# SparkFun_RTK_Facet_L-Band_-_Main.net
KiCad netlist of a schematic drawn in EAGLE
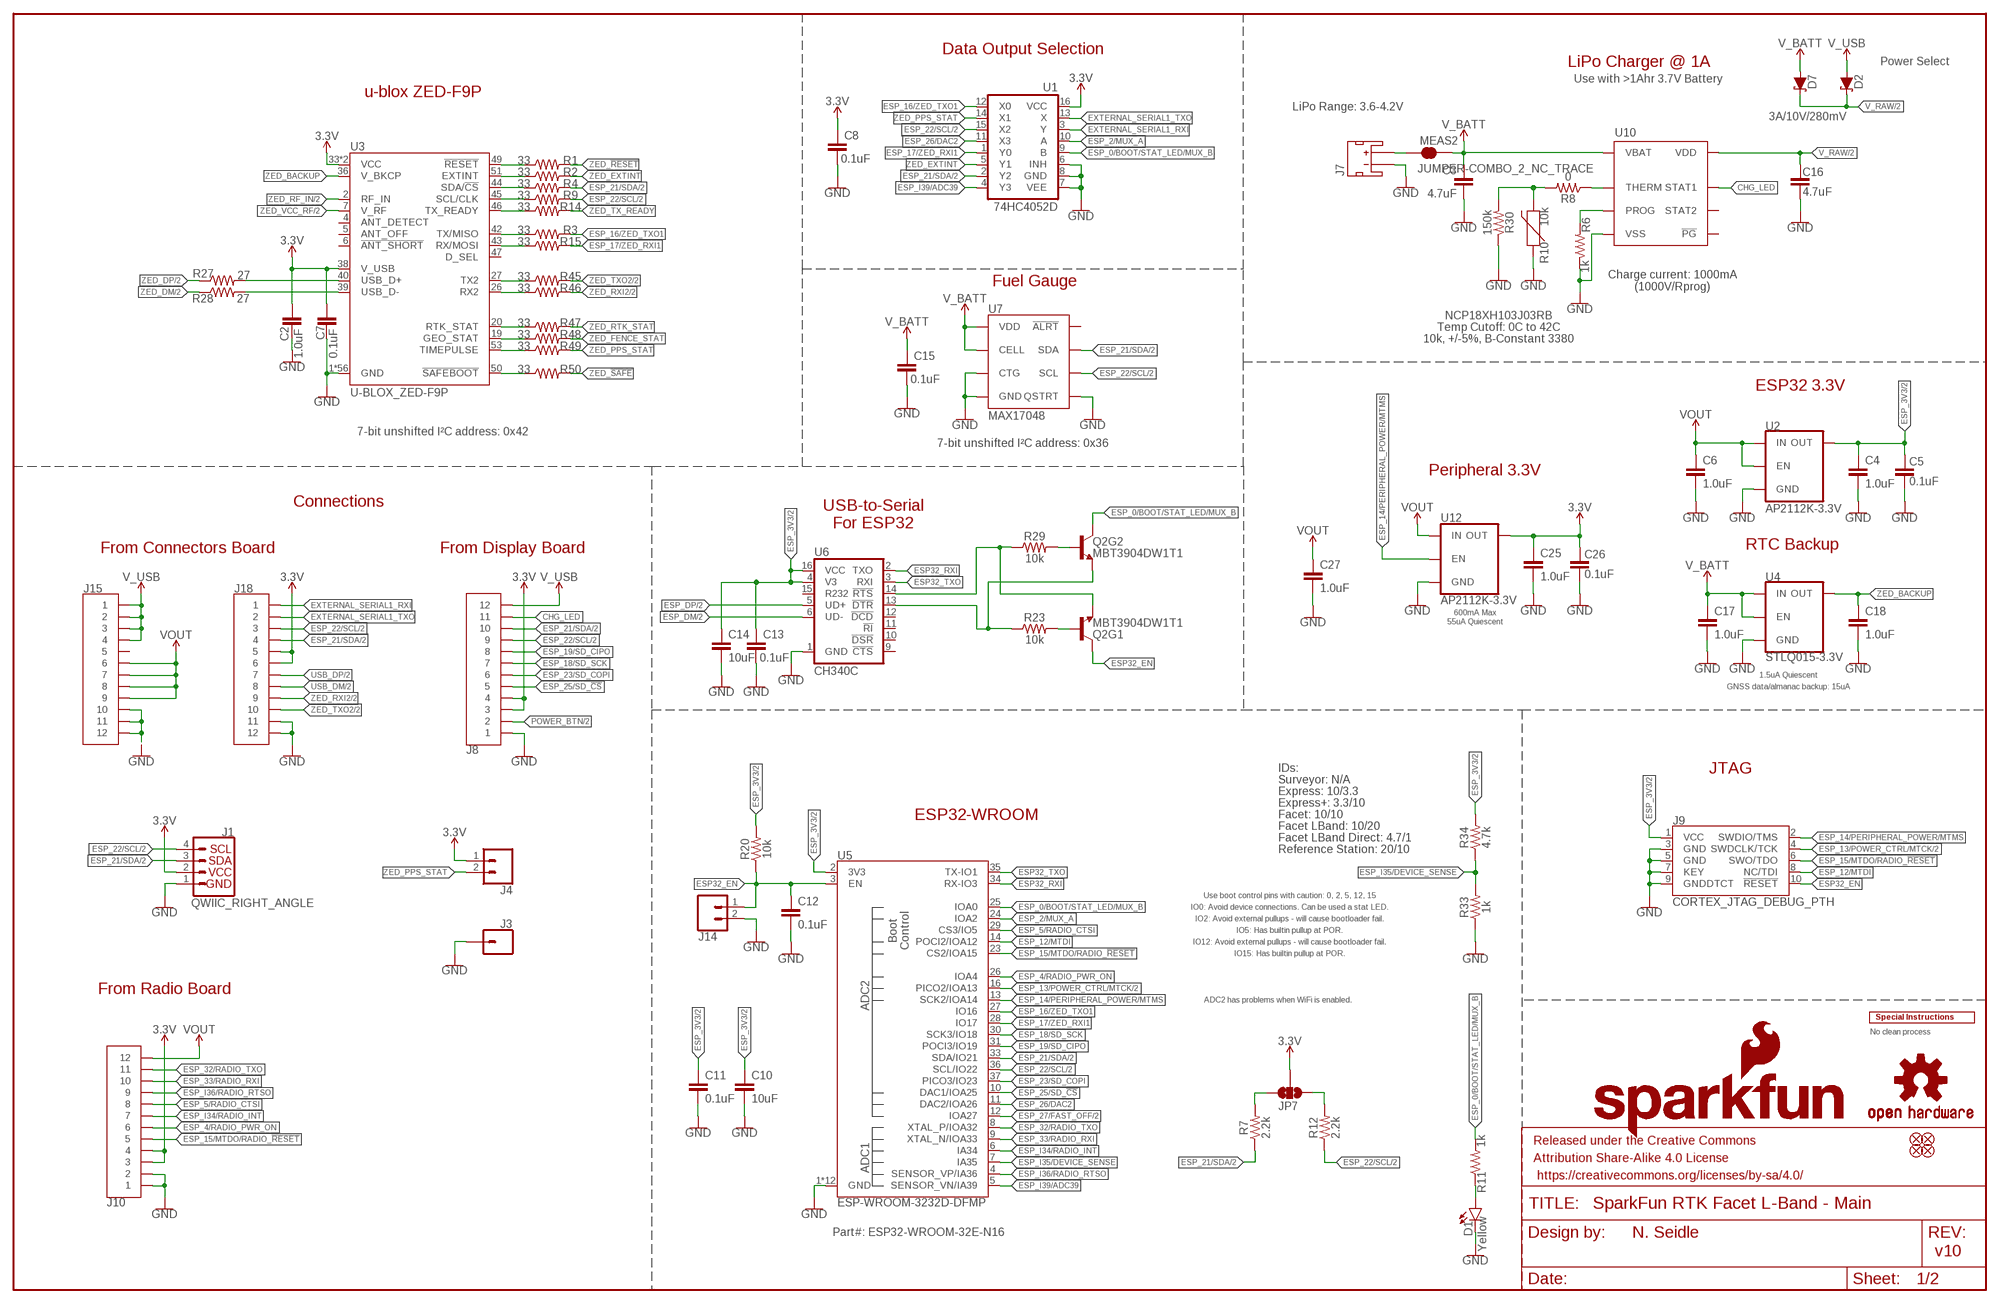
[diagram p0: schematic, sheet 1]
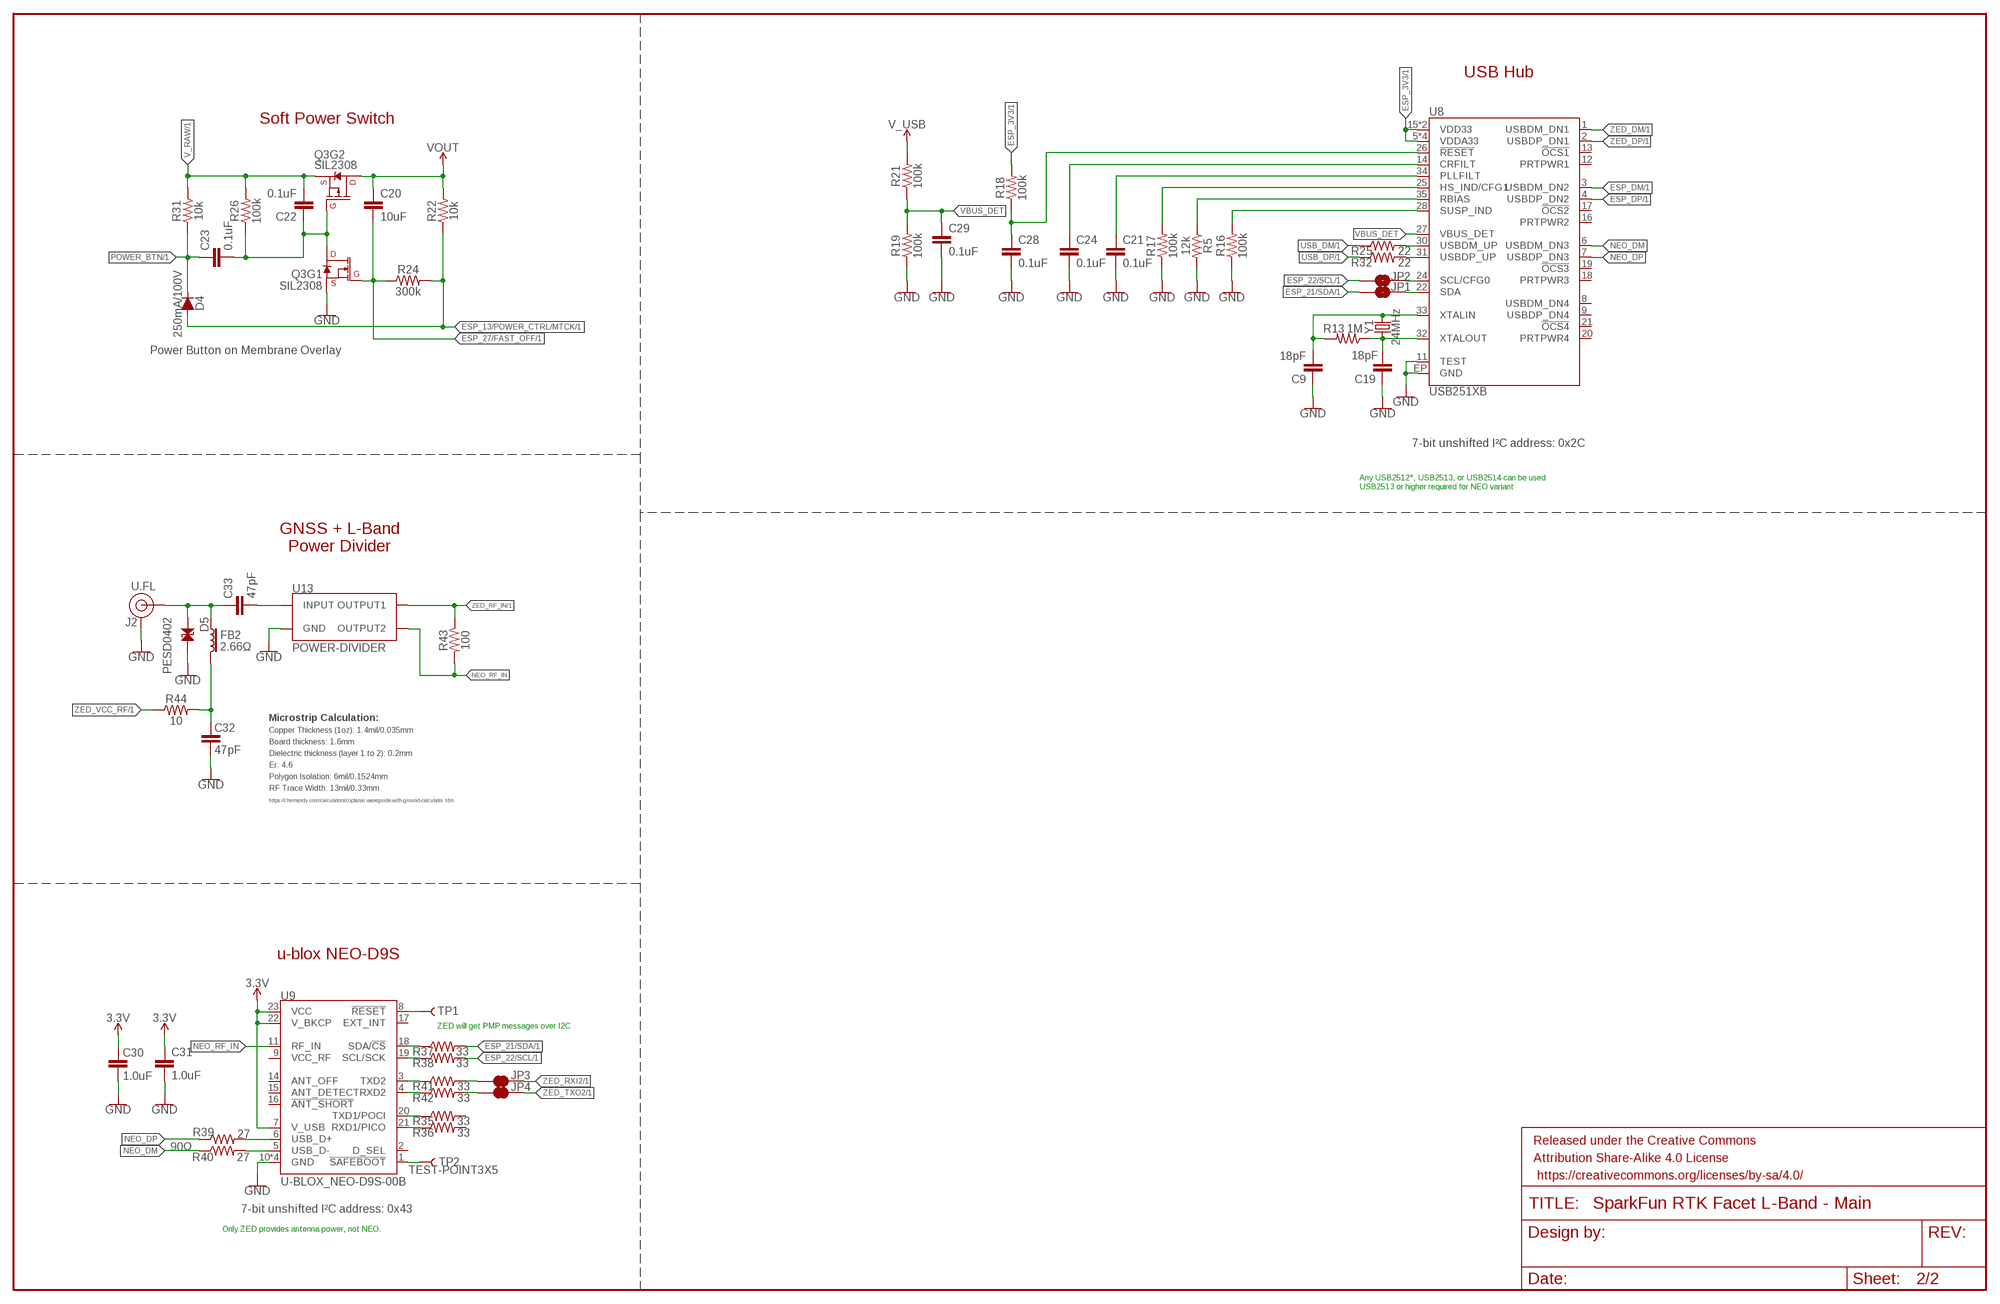
[diagram p1: schematic, sheet 2]

(export (version "E")
  (design (tool "Eeschema 10.0.6"))
  (components
    (comp (ref "C2")
      (value "1.0uF")
      (footprint "eagle-import:0603")
      (libsource (lib "eagle-import") (part "1.0UF-0603-16V-10%-X7R"))
    )
    (comp (ref "C3")
      (value "4.7uF")
      (footprint "eagle-import:0603")
      (libsource (lib "eagle-import") (part "4.7UF-0603-35V-(20%)"))
    )
    (comp (ref "C4")
      (value "1.0uF")
      (footprint "eagle-import:0603")
      (libsource (lib "eagle-import") (part "1.0UF-0603-16V-10%-X7R"))
    )
    (comp (ref "C5")
      (value "0.1uF")
      (footprint "eagle-import:0603")
      (libsource (lib "eagle-import") (part "0.1UF-0603-25V-5%"))
    )
    (comp (ref "C6")
      (value "1.0uF")
      (footprint "eagle-import:0603")
      (libsource (lib "eagle-import") (part "1.0UF-0603-16V-10%-X7R"))
    )
    (comp (ref "C7")
      (value "0.1uF")
      (footprint "eagle-import:0603")
      (libsource (lib "eagle-import") (part "0.1UF-0603-25V-5%"))
    )
    (comp (ref "C8")
      (value "0.1uF")
      (footprint "eagle-import:0603")
      (libsource (lib "eagle-import") (part "0.1UF-0603-25V-(+80/-20%)"))
    )
    (comp (ref "C10")
      (value "10uF")
      (footprint "eagle-import:0603")
      (libsource (lib "eagle-import") (part "10UF-0603-6.3V-20%"))
    )
    (comp (ref "C11")
      (value "0.1uF")
      (footprint "eagle-import:0603")
      (libsource (lib "eagle-import") (part "0.1UF-0603-25V-(+80/-20%)"))
    )
    (comp (ref "C12")
      (value "0.1uF")
      (footprint "eagle-import:0603")
      (libsource (lib "eagle-import") (part "0.1UF-0603-25V-(+80/-20%)"))
    )
    (comp (ref "C13")
      (value "0.1uF")
      (footprint "eagle-import:0603")
      (libsource (lib "eagle-import") (part "0.1UF-0603-25V-(+80/-20%)"))
    )
    (comp (ref "C14")
      (value "10uF")
      (footprint "eagle-import:0603")
      (libsource (lib "eagle-import") (part "10UF-0603-6.3V-20%"))
    )
    (comp (ref "C15")
      (value "0.1uF")
      (footprint "eagle-import:0603")
      (libsource (lib "eagle-import") (part "0.1UF-0603-25V-(+80/-20%)"))
    )
    (comp (ref "C16")
      (value "4.7uF")
      (footprint "eagle-import:0603")
      (libsource (lib "eagle-import") (part "4.7UF-0603-35V-(20%)"))
    )
    (comp (ref "C17")
      (value "1.0uF")
      (footprint "eagle-import:0603")
      (libsource (lib "eagle-import") (part "1.0UF-0603-16V-10%-X7R"))
    )
    (comp (ref "C18")
      (value "1.0uF")
      (footprint "eagle-import:0603")
      (libsource (lib "eagle-import") (part "1.0UF-0603-16V-10%-X7R"))
    )
    (comp (ref "C25")
      (value "1.0uF")
      (footprint "eagle-import:0603")
      (libsource (lib "eagle-import") (part "1.0UF-0603-16V-10%-X7R"))
    )
    (comp (ref "C26")
      (value "0.1uF")
      (footprint "eagle-import:0603")
      (libsource (lib "eagle-import") (part "0.1UF-0603-25V-5%"))
    )
    (comp (ref "C27")
      (value "1.0uF")
      (footprint "eagle-import:0603")
      (libsource (lib "eagle-import") (part "1.0UF-0603-16V-10%-X7R"))
    )
    (comp (ref "D1")
      (value "Yellow")
      (footprint "eagle-import:LED-0603")
      (libsource (lib "eagle-import") (part "LED-YELLOW0603"))
    )
    (comp (ref "D2")
      (value "3A/10V/280mV")
      (footprint "eagle-import:SOD-323")
      (libsource (lib "eagle-import") (part "DIODE-SCHOTTKY-BAT60A"))
    )
    (comp (ref "D7")
      (value "3A/10V/280mV")
      (footprint "eagle-import:SOD-323")
      (libsource (lib "eagle-import") (part "DIODE-SCHOTTKY-BAT60A"))
    )
    (comp (ref "FRAME2")
      (value "FRAME-LEDGER")
      (footprint "eagle-import:CREATIVE_COMMONS")
      (libsource (lib "eagle-import") (part "FRAME-LEDGER"))
    )
    (comp (ref "J1")
      (value "QWIIC_RIGHT_ANGLE")
      (footprint "eagle-import:JST04_1MM_RA")
      (libsource (lib "eagle-import") (part "QWIIC_CONNECTORJS-1MM"))
    )
    (comp (ref "J3")
      (value "CONN_01PTH_NO_SILK_YES_STOP")
      (footprint "eagle-import:1X01_NO_SILK")
      (libsource (lib "eagle-import") (part "CONN_01PTH_NO_SILK_YES_STOP"))
    )
    (comp (ref "J4")
      (value "CONN_021X02_NO_SILK")
      (footprint "eagle-import:1X02_NO_SILK")
      (libsource (lib "eagle-import") (part "CONN_021X02_NO_SILK"))
    )
    (comp (ref "J7")
      (value "JST_2MM_MALE")
      (footprint "eagle-import:JST-2-SMD")
      (libsource (lib "eagle-import") (part "JST_2MM_MALE"))
    )
    (comp (ref "J8")
      (value "FPC_12_0.5MM_BACKFLIP")
      (footprint "eagle-import:FPC_12_DOUBLESIDED_BACKFLIP")
      (libsource (lib "eagle-import") (part "FPC_12_0.5MM_BACKFLIP"))
    )
    (comp (ref "J9")
      (value "CORTEX_JTAG_DEBUG_PTH")
      (footprint "eagle-import:2X5-PTH-1.27MM")
      (libsource (lib "eagle-import") (part "CORTEX_JTAG_DEBUG_PTH"))
    )
    (comp (ref "J10")
      (value "FPC_12_0.5MM_BACKFLIP")
      (footprint "eagle-import:FPC_12_DOUBLESIDED_BACKFLIP")
      (libsource (lib "eagle-import") (part "FPC_12_0.5MM_BACKFLIP"))
    )
    (comp (ref "J14")
      (value "CONN_021X02_NO_SILK")
      (footprint "eagle-import:1X02_NO_SILK")
      (libsource (lib "eagle-import") (part "CONN_021X02_NO_SILK"))
    )
    (comp (ref "J15")
      (value "FPC_12_0.5MM_BACKFLIP")
      (footprint "eagle-import:FPC_12_DOUBLESIDED_BACKFLIP")
      (libsource (lib "eagle-import") (part "FPC_12_0.5MM_BACKFLIP"))
    )
    (comp (ref "J18")
      (value "FPC_12_0.5MM_BACKFLIP")
      (footprint "eagle-import:FPC_12_DOUBLESIDED_BACKFLIP")
      (libsource (lib "eagle-import") (part "FPC_12_0.5MM_BACKFLIP"))
    )
    (comp (ref "JP7")
      (value "JUMPER-SMT_3_NO_SILK")
      (footprint "eagle-import:SMT-JUMPER_3_NO_SILK")
      (libsource (lib "eagle-import") (part "JUMPER-SMT_3_NO_SILK"))
    )
    (comp (ref "JP21")
      (value "FIDUCIALUFIDUCIAL")
      (footprint "eagle-import:FIDUCIAL-MICRO")
      (libsource (lib "eagle-import") (part "FIDUCIALUFIDUCIAL"))
    )
    (comp (ref "JP61")
      (value "FIDUCIALUFIDUCIAL")
      (footprint "eagle-import:FIDUCIAL-MICRO")
      (libsource (lib "eagle-import") (part "FIDUCIALUFIDUCIAL"))
    )
    (comp (ref "JP71")
      (value "FIDUCIALUFIDUCIAL")
      (footprint "eagle-import:FIDUCIAL-MICRO")
      (libsource (lib "eagle-import") (part "FIDUCIALUFIDUCIAL"))
    )
    (comp (ref "JP81")
      (value "FIDUCIALUFIDUCIAL")
      (footprint "eagle-import:FIDUCIAL-MICRO")
      (libsource (lib "eagle-import") (part "FIDUCIALUFIDUCIAL"))
    )
    (comp (ref "LOGO1")
      (value "OSHW-LOGOMINI")
      (footprint "eagle-import:OSHW-LOGO-MINI")
      (libsource (lib "eagle-import") (part "OSHW-LOGOMINI"))
    )
    (comp (ref "LOGO2")
      (value "SFE_LOGO_NAME_FLAME.1_INCH")
      (footprint "eagle-import:SFE_LOGO_NAME_FLAME_.1")
      (libsource (lib "eagle-import") (part "SFE_LOGO_NAME_FLAME.1_INCH"))
    )
    (comp (ref "MEAS2")
      (value "JUMPER-COMBO_2_NC_TRACE")
      (footprint "eagle-import:COMBO-JUMPER_2_NC_TRACE")
      (libsource (lib "eagle-import") (part "JUMPER-COMBO_2_NC_TRACE"))
    )
    (comp (ref "Q2")
      (value "MBT3904DW1T1")
      (footprint "eagle-import:SC70-6")
      (libsource (lib "eagle-import") (part "TRANS_NPN_DUAL-MBT3904DW1T1"))
    )
    (comp (ref "R1")
      (value "33")
      (footprint "eagle-import:0603")
      (libsource (lib "eagle-import") (part "33OHM-0603-1/10W-1%"))
    )
    (comp (ref "R2")
      (value "33")
      (footprint "eagle-import:0603")
      (libsource (lib "eagle-import") (part "33OHM-0603-1/10W-1%"))
    )
    (comp (ref "R3")
      (value "33")
      (footprint "eagle-import:0603")
      (libsource (lib "eagle-import") (part "33OHM-0603-1/10W-1%"))
    )
    (comp (ref "R4")
      (value "33")
      (footprint "eagle-import:0603")
      (libsource (lib "eagle-import") (part "33OHM-0603-1/10W-1%"))
    )
    (comp (ref "R6")
      (value "1k")
      (footprint "eagle-import:0603")
      (libsource (lib "eagle-import") (part "1KOHM-0603-1/10W-1%"))
    )
    (comp (ref "R7")
      (value "2.2k")
      (footprint "eagle-import:0603")
      (libsource (lib "eagle-import") (part "2.2KOHM-0603-1/10W-1%"))
    )
    (comp (ref "R8")
      (value "0")
      (footprint "eagle-import:0603")
      (libsource (lib "eagle-import") (part "0OHM-0603-1/10W"))
    )
    (comp (ref "R9")
      (value "33")
      (footprint "eagle-import:0603")
      (libsource (lib "eagle-import") (part "33OHM-0603-1/10W-1%"))
    )
    (comp (ref "R10")
      (value "10k")
      (footprint "eagle-import:0603")
      (libsource (lib "eagle-import") (part "NTC-THERMISTOR-0603"))
    )
    (comp (ref "R11")
      (value "1k")
      (footprint "eagle-import:0603")
      (libsource (lib "eagle-import") (part "1KOHM-0603-1/10W-1%"))
    )
    (comp (ref "R12")
      (value "2.2k")
      (footprint "eagle-import:0603")
      (libsource (lib "eagle-import") (part "2.2KOHM-0603-1/10W-1%"))
    )
    (comp (ref "R14")
      (value "33")
      (footprint "eagle-import:0603")
      (libsource (lib "eagle-import") (part "33OHM-0603-1/10W-1%"))
    )
    (comp (ref "R15")
      (value "33")
      (footprint "eagle-import:0603")
      (libsource (lib "eagle-import") (part "33OHM-0603-1/10W-1%"))
    )
    (comp (ref "R20")
      (value "10k")
      (footprint "eagle-import:0603")
      (libsource (lib "eagle-import") (part "10KOHM-0603-1/10W-1%"))
    )
    (comp (ref "R23")
      (value "10k")
      (footprint "eagle-import:0603")
      (libsource (lib "eagle-import") (part "10KOHM-0603-1/10W-1%"))
    )
    (comp (ref "R27")
      (value "27")
      (footprint "eagle-import:0603")
      (libsource (lib "eagle-import") (part "27OHM-0603-1/10W-1%"))
    )
    (comp (ref "R28")
      (value "27")
      (footprint "eagle-import:0603")
      (libsource (lib "eagle-import") (part "27OHM-0603-1/10W-1%"))
    )
    (comp (ref "R29")
      (value "10k")
      (footprint "eagle-import:0603")
      (libsource (lib "eagle-import") (part "10KOHM-0603-1/10W-1%"))
    )
    (comp (ref "R30")
      (value "150k")
      (footprint "eagle-import:0603")
      (libsource (lib "eagle-import") (part "150KOHM-0603-1/10W-1%"))
    )
    (comp (ref "R33")
      (value "1k")
      (footprint "eagle-import:0603")
      (libsource (lib "eagle-import") (part "1KOHM-0603-1/10W-1%"))
    )
    (comp (ref "R34")
      (value "4.7k")
      (footprint "eagle-import:0603")
      (libsource (lib "eagle-import") (part "4.7KOHM-0603-1/10W-1%"))
    )
    (comp (ref "R45")
      (value "33")
      (footprint "eagle-import:0603")
      (libsource (lib "eagle-import") (part "33OHM-0603-1/10W-1%"))
    )
    (comp (ref "R46")
      (value "33")
      (footprint "eagle-import:0603")
      (libsource (lib "eagle-import") (part "33OHM-0603-1/10W-1%"))
    )
    (comp (ref "R47")
      (value "33")
      (footprint "eagle-import:0603")
      (libsource (lib "eagle-import") (part "33OHM-0603-1/10W-1%"))
    )
    (comp (ref "R48")
      (value "33")
      (footprint "eagle-import:0603")
      (libsource (lib "eagle-import") (part "33OHM-0603-1/10W-1%"))
    )
    (comp (ref "R49")
      (value "33")
      (footprint "eagle-import:0603")
      (libsource (lib "eagle-import") (part "33OHM-0603-1/10W-1%"))
    )
    (comp (ref "R50")
      (value "33")
      (footprint "eagle-import:0603")
      (libsource (lib "eagle-import") (part "33OHM-0603-1/10W-1%"))
    )
    (comp (ref "U$2")
      (value "SPECIAL_INSTRUCTIONS-ORDERING")
      (footprint "eagle-import:ORDERING_INSTRUCTIONS")
      (libsource (lib "eagle-import") (part "SPECIAL_INSTRUCTIONS-ORDERING"))
    )
    (comp (ref "U1")
      (value "74HC4052D")
      (footprint "eagle-import:SO16")
      (libsource (lib "eagle-import") (part "744052DHC"))
    )
    (comp (ref "U2")
      (value "AP2112K-3.3V")
      (footprint "eagle-import:SOT23-5")
      (libsource (lib "eagle-import") (part "V_REG_AP2112K-3.3V"))
    )
    (comp (ref "U3")
      (value "U-BLOX_ZED-F9P")
      (footprint "eagle-import:ZED-F9P")
      (libsource (lib "eagle-import") (part "U-BLOX_ZED-F9P"))
    )
    (comp (ref "U4")
      (value "STLQ015-3.3V")
      (footprint "eagle-import:SOT23-5")
      (libsource (lib "eagle-import") (part "STLQ015-3.3V"))
    )
    (comp (ref "U5")
      (value "ESP-WROOM-3232D-DFMP")
      (footprint "eagle-import:ESP-WROOM-32D-DFM_PASTE")
      (libsource (lib "eagle-import") (part "ESP-WROOM-3232D-DFMP"))
    )
    (comp (ref "U6")
      (value "CH340C")
      (footprint "eagle-import:SO016")
      (libsource (lib "eagle-import") (part "CH340C"))
    )
    (comp (ref "U7")
      (value "MAX17048")
      (footprint "eagle-import:DFN-8")
      (libsource (lib "eagle-import") (part "MAX17048DFN8"))
    )
    (comp (ref "U10")
      (value "MCP73833MSOP")
      (footprint "eagle-import:MSOP10")
      (libsource (lib "eagle-import") (part "MCP73833MSOP"))
    )
    (comp (ref "U12")
      (value "AP2112K-3.3V")
      (footprint "eagle-import:SOT23-5")
      (libsource (lib "eagle-import") (part "V_REG_AP2112K-3.3V"))
    )
    (comp (ref "C9")
      (value "18pF")
      (footprint "eagle-import:0603")
      (libsource (lib "eagle-import") (part "18PF-0603-50V-5%"))
    )
    (comp (ref "C19")
      (value "18pF")
      (footprint "eagle-import:0603")
      (libsource (lib "eagle-import") (part "18PF-0603-50V-5%"))
    )
    (comp (ref "C20")
      (value "10uF")
      (footprint "eagle-import:0603")
      (libsource (lib "eagle-import") (part "10UF-0603-6.3V-20%"))
    )
    (comp (ref "C21")
      (value "0.1uF")
      (footprint "eagle-import:0603")
      (libsource (lib "eagle-import") (part "0.1UF-0603-25V-5%"))
    )
    (comp (ref "C22")
      (value "0.1uF")
      (footprint "eagle-import:0603")
      (libsource (lib "eagle-import") (part "0.1UF-0603-25V-5%"))
    )
    (comp (ref "C23")
      (value "0.1uF")
      (footprint "eagle-import:0603")
      (libsource (lib "eagle-import") (part "0.1UF-0603-25V-5%"))
    )
    (comp (ref "C24")
      (value "0.1uF")
      (footprint "eagle-import:0603")
      (libsource (lib "eagle-import") (part "0.1UF-0603-25V-5%"))
    )
    (comp (ref "C28")
      (value "0.1uF")
      (footprint "eagle-import:0603")
      (libsource (lib "eagle-import") (part "0.1UF-0603-25V-5%"))
    )
    (comp (ref "C29")
      (value "0.1uF")
      (footprint "eagle-import:0603")
      (libsource (lib "eagle-import") (part "0.1UF-0603-25V-5%"))
    )
    (comp (ref "C30")
      (value "1.0uF")
      (footprint "eagle-import:0603")
      (libsource (lib "eagle-import") (part "1.0UF-0603-16V-10%"))
    )
    (comp (ref "C31")
      (value "1.0uF")
      (footprint "eagle-import:0603")
      (libsource (lib "eagle-import") (part "1.0UF-0603-16V-10%"))
    )
    (comp (ref "C32")
      (value "47pF")
      (footprint "eagle-import:0402-TIGHT")
      (libsource (lib "eagle-import") (part "47PF-0402_TIGHT-25V-5%-X7R"))
    )
    (comp (ref "C33")
      (value "47pF")
      (footprint "eagle-import:0402-TIGHT")
      (libsource (lib "eagle-import") (part "47PF-0402_TIGHT-25V-5%-X7R"))
    )
    (comp (ref "D4")
      (value "250mA/100V")
      (footprint "eagle-import:SOD-323")
      (libsource (lib "eagle-import") (part "DIODE-BAS16J"))
    )
    (comp (ref "D5")
      (value "PESD0402")
      (footprint "eagle-import:0402-TIGHT")
      (libsource (lib "eagle-import") (part "PESD0402-0402T"))
    )
    (comp (ref "FB2")
      (value "2.66Ω")
      (footprint "eagle-import:0402-TIGHT")
      (libsource (lib "eagle-import") (part "FERRITE_BEAD-0402-2.66Ω-1GHZ"))
    )
    (comp (ref "FRAME1")
      (value "FRAME-LEDGER")
      (footprint "eagle-import:CREATIVE_COMMONS")
      (libsource (lib "eagle-import") (part "FRAME-LEDGER"))
    )
    (comp (ref "J2")
      (value "U.FL")
      (footprint "eagle-import:U.FL")
      (libsource (lib "eagle-import") (part "U.FL2PIN"))
    )
    (comp (ref "JP1")
      (value "JUMPER-SMT_2_NO_SILK")
      (footprint "eagle-import:SMT-JUMPER_2_NO_SILK")
      (libsource (lib "eagle-import") (part "JUMPER-SMT_2_NO_SILK"))
    )
    (comp (ref "JP2")
      (value "JUMPER-SMT_2_NO_SILK")
      (footprint "eagle-import:SMT-JUMPER_2_NO_SILK")
      (libsource (lib "eagle-import") (part "JUMPER-SMT_2_NO_SILK"))
    )
    (comp (ref "JP3")
      (value "JUMPER-SMT_2_NC_TRACE_SILK")
      (footprint "eagle-import:SMT-JUMPER_2_NC_TRACE_SILK")
      (libsource (lib "eagle-import") (part "JUMPER-SMT_2_NC_TRACE_SILK"))
    )
    (comp (ref "JP4")
      (value "JUMPER-SMT_2_NC_TRACE_SILK")
      (footprint "eagle-import:SMT-JUMPER_2_NC_TRACE_SILK")
      (libsource (lib "eagle-import") (part "JUMPER-SMT_2_NC_TRACE_SILK"))
    )
    (comp (ref "Q3")
      (value "SIL2308")
      (footprint "eagle-import:SOT26")
      (libsource (lib "eagle-import") (part "MOSFET_COMPLIMENTARY_PAIR-SIL2308"))
    )
    (comp (ref "R5")
      (value "12k")
      (footprint "eagle-import:0603")
      (libsource (lib "eagle-import") (part "12KOHM-0603-1/10W-1%"))
    )
    (comp (ref "R13")
      (value "1M")
      (footprint "eagle-import:0603")
      (libsource (lib "eagle-import") (part "1MOHM-0603-1/4W-5%"))
    )
    (comp (ref "R16")
      (value "100k")
      (footprint "eagle-import:0603")
      (libsource (lib "eagle-import") (part "100KOHM-0603-1/10W-1%"))
    )
    (comp (ref "R17")
      (value "100k")
      (footprint "eagle-import:0603")
      (libsource (lib "eagle-import") (part "100KOHM-0603-1/10W-1%"))
    )
    (comp (ref "R18")
      (value "100k")
      (footprint "eagle-import:0603")
      (libsource (lib "eagle-import") (part "100KOHM-0603-1/10W-1%"))
    )
    (comp (ref "R19")
      (value "100k")
      (footprint "eagle-import:0603")
      (libsource (lib "eagle-import") (part "100KOHM-0603-1/10W-1%"))
    )
    (comp (ref "R21")
      (value "100k")
      (footprint "eagle-import:0603")
      (libsource (lib "eagle-import") (part "100KOHM-0603-1/10W-1%"))
    )
    (comp (ref "R22")
      (value "10k")
      (footprint "eagle-import:0603")
      (libsource (lib "eagle-import") (part "10KOHM-0603-1/10W-1%"))
    )
    (comp (ref "R24")
      (value "300k")
      (footprint "eagle-import:0603")
      (libsource (lib "eagle-import") (part "300KOHM-0603-1/10W-1%"))
    )
    (comp (ref "R25")
      (value "22")
      (footprint "eagle-import:0603")
      (libsource (lib "eagle-import") (part "22OHM-0603-1/10W-1%"))
    )
    (comp (ref "R26")
      (value "100k")
      (footprint "eagle-import:0603")
      (libsource (lib "eagle-import") (part "100KOHM-0603-1/10W-1%"))
    )
    (comp (ref "R31")
      (value "10k")
      (footprint "eagle-import:0603")
      (libsource (lib "eagle-import") (part "10KOHM-0603-1/10W-1%"))
    )
    (comp (ref "R32")
      (value "22")
      (footprint "eagle-import:0603")
      (libsource (lib "eagle-import") (part "22OHM-0603-1/10W-1%"))
    )
    (comp (ref "R35")
      (value "33")
      (footprint "eagle-import:0603")
      (libsource (lib "eagle-import") (part "33OHM-0603-1/10W-1%"))
    )
    (comp (ref "R36")
      (value "33")
      (footprint "eagle-import:0603")
      (libsource (lib "eagle-import") (part "33OHM-0603-1/10W-1%"))
    )
    (comp (ref "R37")
      (value "33")
      (footprint "eagle-import:0603")
      (libsource (lib "eagle-import") (part "33OHM-0603-1/10W-1%"))
    )
    (comp (ref "R38")
      (value "33")
      (footprint "eagle-import:0603")
      (libsource (lib "eagle-import") (part "33OHM-0603-1/10W-1%"))
    )
    (comp (ref "R39")
      (value "27")
      (footprint "eagle-import:0603")
      (libsource (lib "eagle-import") (part "27OHM-0603-1/10W-1%"))
    )
    (comp (ref "R40")
      (value "27")
      (footprint "eagle-import:0603")
      (libsource (lib "eagle-import") (part "27OHM-0603-1/10W-1%"))
    )
    (comp (ref "R41")
      (value "33")
      (footprint "eagle-import:0603")
      (libsource (lib "eagle-import") (part "33OHM-0603-1/10W-1%"))
    )
    (comp (ref "R42")
      (value "33")
      (footprint "eagle-import:0603")
      (libsource (lib "eagle-import") (part "33OHM-0603-1/10W-1%"))
    )
    (comp (ref "R43")
      (value "100")
      (footprint "eagle-import:0603")
      (libsource (lib "eagle-import") (part "100OHM-0603-1/10W-1%"))
    )
    (comp (ref "R44")
      (value "10")
      (footprint "eagle-import:0402-TIGHT")
      (libsource (lib "eagle-import") (part "10OHM-0402-1/16W-5%"))
    )
    (comp (ref "TP1")
      (value "TEST-POINT3X5")
      (footprint "eagle-import:PAD.03X.05")
      (libsource (lib "eagle-import") (part "TEST-POINT3X5"))
    )
    (comp (ref "TP2")
      (value "TEST-POINT3X5")
      (footprint "eagle-import:PAD.03X.05")
      (libsource (lib "eagle-import") (part "TEST-POINT3X5"))
    )
    (comp (ref "U8")
      (value "USB251XB")
      (footprint "eagle-import:QFN-36")
      (libsource (lib "eagle-import") (part "USB251XB"))
    )
    (comp (ref "U9")
      (value "U-BLOX_NEO-D9S-00B")
      (footprint "eagle-import:NEO-M9N_M8T_M8U_D9S_F9P")
      (libsource (lib "eagle-import") (part "U-BLOX_NEO-D9S-00B"))
    )
    (comp (ref "U13")
      (value "POWER-DIVIDER")
      (footprint "eagle-import:PD0922J5050S2HF_ANA")
      (fields (field (name "MANUFACTURER_PART_NUMBER") "PD0922J5050S2HF"))
      (libsource (lib "eagle-import") (part "POWER-DIVIDER"))
    )
    (comp (ref "Y1")
      (value "24MHz")
      (footprint "eagle-import:CRYSTAL-SMD-2.0X1.6MM")
      (libsource (lib "eagle-import") (part "CRYSTAL-24MHZ-SMD-2.0X1.6MM"))
    )
  )
  (nets
    (net (code "1") (name "3.3V") (class "Default")
      (node (ref "C2") (pin "1") (pinfunction "1_1") (pintype "passive"))
      (node (ref "C25") (pin "1") (pinfunction "1_1") (pintype "passive"))
      (node (ref "C26") (pin "2") (pinfunction "2_2") (pintype "passive"))
      (node (ref "C30") (pin "1") (pinfunction "1_1") (pintype "passive"))
      (node (ref "C31") (pin "1") (pinfunction "1_1") (pintype "passive"))
      (node (ref "C7") (pin "2") (pinfunction "2_2") (pintype "passive"))
      (node (ref "C8") (pin "1") (pinfunction "1_1") (pintype "passive"))
      (node (ref "J1") (pin "2") (pinfunction "2_2") (pintype "power_in"))
      (node (ref "J10") (pin "3") (pinfunction "3_3") (pintype "bidirectional"))
      (node (ref "J10") (pin "4") (pinfunction "4_4") (pintype "bidirectional"))
      (node (ref "J18") (pin "5") (pinfunction "5_5") (pintype "bidirectional"))
      (node (ref "J18") (pin "6") (pinfunction "6_6") (pintype "bidirectional"))
      (node (ref "J4") (pin "1") (pinfunction "1_1") (pintype "passive"))
      (node (ref "J8") (pin "3") (pinfunction "3_3") (pintype "bidirectional"))
      (node (ref "J8") (pin "4") (pinfunction "4_4") (pintype "bidirectional"))
      (node (ref "JP7") (pin "2") (pinfunction "2_2") (pintype "passive"))
      (node (ref "U1") (pin "16") (pinfunction "VCC_16") (pintype "power_in"))
      (node (ref "U12") (pin "5") (pinfunction "OUT_5") (pintype "passive"))
      (node (ref "U3") (pin "33") (pinfunction "VCC_33") (pintype "bidirectional"))
      (node (ref "U3") (pin "34") (pinfunction "VCC_34") (pintype "bidirectional"))
      (node (ref "U3") (pin "38") (pinfunction "V_USB_38") (pintype "bidirectional"))
      (node (ref "U9") (pin "22") (pinfunction "V_BKCP_22") (pintype "power_in"))
      (node (ref "U9") (pin "23") (pinfunction "VCC_23") (pintype "power_in"))
      (node (ref "U9") (pin "7") (pinfunction "V_USB_7") (pintype "power_in"))
    )
    (net (code "2") (name "CHG_LED") (class "Default")
      (node (ref "J8") (pin "11") (pinfunction "11_11") (pintype "bidirectional"))
      (node (ref "U10") (pin "3") (pinfunction "STAT1_3") (pintype "bidirectional"))
    )
    (net (code "3") (name "ESP32_EN") (class "Default")
      (node (ref "C12") (pin "1") (pinfunction "1_1") (pintype "passive"))
      (node (ref "J14") (pin "1") (pinfunction "1_1") (pintype "passive"))
      (node (ref "J9") (pin "10") (pinfunction "~{RESET}_10") (pintype "bidirectional"))
      (node (ref "Q2") (pin "3") (pinfunction "C_3") (pintype "passive"))
      (node (ref "R20") (pin "1") (pinfunction "1_1") (pintype "passive"))
      (node (ref "U5") (pin "3") (pinfunction "EN_3") (pintype "bidirectional"))
    )
    (net (code "4") (name "ESP32_RXI") (class "Default")
      (node (ref "U5") (pin "34") (pinfunction "RX-IO3_34") (pintype "bidirectional"))
      (node (ref "U6") (pin "2") (pinfunction "TXO_2") (pintype "bidirectional"))
    )
    (net (code "5") (name "ESP32_TXO") (class "Default")
      (node (ref "U5") (pin "35") (pinfunction "TX-IO1_35") (pintype "bidirectional"))
      (node (ref "U6") (pin "3") (pinfunction "RXI_3") (pintype "bidirectional"))
    )
    (net (code "6") (name "ESP_0{slash}BOOT{slash}STAT_LED{slash}MUX_B") (class "Default")
      (node (ref "Q2") (pin "6") (pinfunction "C_6") (pintype "passive"))
      (node (ref "R11") (pin "2") (pinfunction "2_2") (pintype "passive"))
      (node (ref "U1") (pin "9") (pinfunction "B_9") (pintype "input"))
      (node (ref "U5") (pin "25") (pinfunction "IOA0_25") (pintype "bidirectional"))
    )
    (net (code "7") (name "ESP_2{slash}MUX_A") (class "Default")
      (node (ref "U1") (pin "10") (pinfunction "A_10") (pintype "input"))
      (node (ref "U5") (pin "24") (pinfunction "IOA2_24") (pintype "bidirectional"))
    )
    (net (code "8") (name "ESP_3V3") (class "Default")
      (node (ref "C10") (pin "1") (pinfunction "1_1") (pintype "passive"))
      (node (ref "C11") (pin "1") (pinfunction "1_1") (pintype "passive"))
      (node (ref "C13") (pin "1") (pinfunction "1_1") (pintype "passive"))
      (node (ref "C14") (pin "1") (pinfunction "1_1") (pintype "passive"))
      (node (ref "C4") (pin "1") (pinfunction "1_1") (pintype "passive"))
      (node (ref "C5") (pin "2") (pinfunction "2_2") (pintype "passive"))
      (node (ref "J9") (pin "1") (pinfunction "VCC_1") (pintype "bidirectional"))
      (node (ref "R18") (pin "2") (pinfunction "2_2") (pintype "passive"))
      (node (ref "R20") (pin "2") (pinfunction "2_2") (pintype "passive"))
      (node (ref "R34") (pin "2") (pinfunction "2_2") (pintype "passive"))
      (node (ref "U2") (pin "5") (pinfunction "OUT_5") (pintype "passive"))
      (node (ref "U5") (pin "2") (pinfunction "3V3_2") (pintype "bidirectional"))
      (node (ref "U6") (pin "16") (pinfunction "VCC_16") (pintype "bidirectional"))
      (node (ref "U6") (pin "4") (pinfunction "V3_4") (pintype "bidirectional"))
      (node (ref "U8") (pin "10") (pinfunction "VDDA33_10") (pintype "bidirectional"))
      (node (ref "U8") (pin "15") (pinfunction "VDD33_15") (pintype "bidirectional"))
      (node (ref "U8") (pin "23") (pinfunction "VDD33_23") (pintype "bidirectional"))
      (node (ref "U8") (pin "29") (pinfunction "VDDA33_29") (pintype "bidirectional"))
      (node (ref "U8") (pin "36") (pinfunction "VDDA33_36") (pintype "bidirectional"))
      (node (ref "U8") (pin "5") (pinfunction "VDDA33_5") (pintype "bidirectional"))
    )
    (net (code "9") (name "ESP_4{slash}RADIO_PWR_ON") (class "Default")
      (node (ref "J10") (pin "6") (pinfunction "6_6") (pintype "bidirectional"))
      (node (ref "U5") (pin "26") (pinfunction "IOA4_26") (pintype "bidirectional"))
    )
    (net (code "10") (name "ESP_5{slash}RADIO_CTSI") (class "Default")
      (node (ref "J10") (pin "8") (pinfunction "8_8") (pintype "bidirectional"))
      (node (ref "U5") (pin "29") (pinfunction "CS3/IO5_29") (pintype "bidirectional"))
    )
    (net (code "11") (name "ESP_12{slash}MTDI") (class "Default")
      (node (ref "J9") (pin "8") (pinfunction "NC/TDI_8") (pintype "bidirectional"))
      (node (ref "U5") (pin "14") (pinfunction "POCI2/IOA12_14") (pintype "bidirectional"))
    )
    (net (code "12") (name "ESP_13{slash}POWER_CTRL{slash}MTCK") (class "Default")
      (node (ref "D4") (pin "A") (pinfunction "A_A") (pintype "passive"))
      (node (ref "J9") (pin "4") (pinfunction "SWDCLK/TCK_4") (pintype "bidirectional"))
      (node (ref "R22") (pin "1") (pinfunction "1_1") (pintype "passive"))
      (node (ref "R24") (pin "2") (pinfunction "2_2") (pintype "passive"))
      (node (ref "U5") (pin "16") (pinfunction "PICO2/IOA13_16") (pintype "bidirectional"))
    )
    (net (code "13") (name "ESP_14{slash}PERIPHERAL_POWER{slash}MTMS") (class "Default")
      (node (ref "J9") (pin "2") (pinfunction "SWDIO/TMS_2") (pintype "bidirectional"))
      (node (ref "U12") (pin "3") (pinfunction "EN_3") (pintype "input"))
      (node (ref "U5") (pin "13") (pinfunction "SCK2/IOA14_13") (pintype "bidirectional"))
    )
    (net (code "14") (name "ESP_15{slash}MTDO{slash}RADIO_~{RESET}") (class "Default")
      (node (ref "J10") (pin "5") (pinfunction "5_5") (pintype "bidirectional"))
      (node (ref "J9") (pin "6") (pinfunction "SWO/TDO_6") (pintype "bidirectional"))
      (node (ref "U5") (pin "23") (pinfunction "CS2/IOA15_23") (pintype "bidirectional"))
    )
    (net (code "15") (name "ESP_16{slash}ZED_TXO1") (class "Default")
      (node (ref "R3") (pin "2") (pinfunction "2_2") (pintype "passive"))
      (node (ref "U1") (pin "12") (pinfunction "X0_12") (pintype "bidirectional"))
      (node (ref "U5") (pin "27") (pinfunction "IO16_27") (pintype "bidirectional"))
    )
    (net (code "16") (name "ESP_17{slash}ZED_RXI1") (class "Default")
      (node (ref "R15") (pin "2") (pinfunction "2_2") (pintype "passive"))
      (node (ref "U1") (pin "1") (pinfunction "Y0_1") (pintype "bidirectional"))
      (node (ref "U5") (pin "28") (pinfunction "IO17_28") (pintype "bidirectional"))
    )
    (net (code "17") (name "ESP_18{slash}SD_SCK") (class "Default")
      (node (ref "J8") (pin "7") (pinfunction "7_7") (pintype "bidirectional"))
      (node (ref "U5") (pin "30") (pinfunction "SCK3/IO18_30") (pintype "bidirectional"))
    )
    (net (code "18") (name "ESP_19{slash}SD_CIPO") (class "Default")
      (node (ref "J8") (pin "8") (pinfunction "8_8") (pintype "bidirectional"))
      (node (ref "U5") (pin "31") (pinfunction "POCI3/IO19_31") (pintype "bidirectional"))
    )
    (net (code "19") (name "ESP_21{slash}SDA") (class "Default")
      (node (ref "J1") (pin "3") (pinfunction "3_3") (pintype "passive"))
      (node (ref "J18") (pin "4") (pinfunction "4_4") (pintype "bidirectional"))
      (node (ref "J8") (pin "10") (pinfunction "10_10") (pintype "bidirectional"))
      (node (ref "JP1") (pin "1") (pinfunction "1_1") (pintype "passive"))
      (node (ref "R37") (pin "2") (pinfunction "2_2") (pintype "passive"))
      (node (ref "R4") (pin "2") (pinfunction "2_2") (pintype "passive"))
      (node (ref "R7") (pin "1") (pinfunction "1_1") (pintype "passive"))
      (node (ref "U1") (pin "2") (pinfunction "Y2_2") (pintype "bidirectional"))
      (node (ref "U5") (pin "33") (pinfunction "SDA/IO21_33") (pintype "bidirectional"))
      (node (ref "U7") (pin "8") (pinfunction "SDA_8") (pintype "input"))
    )
    (net (code "20") (name "ESP_22{slash}SCL") (class "Default")
      (node (ref "J1") (pin "4") (pinfunction "4_4") (pintype "passive"))
      (node (ref "J18") (pin "3") (pinfunction "3_3") (pintype "bidirectional"))
      (node (ref "J8") (pin "9") (pinfunction "9_9") (pintype "bidirectional"))
      (node (ref "JP2") (pin "1") (pinfunction "1_1") (pintype "passive"))
      (node (ref "R12") (pin "1") (pinfunction "1_1") (pintype "passive"))
      (node (ref "R38") (pin "2") (pinfunction "2_2") (pintype "passive"))
      (node (ref "R9") (pin "2") (pinfunction "2_2") (pintype "passive"))
      (node (ref "U1") (pin "15") (pinfunction "X2_15") (pintype "bidirectional"))
      (node (ref "U5") (pin "36") (pinfunction "SCL/IO22_36") (pintype "bidirectional"))
      (node (ref "U7") (pin "7") (pinfunction "SCL_7") (pintype "output"))
    )
    (net (code "21") (name "ESP_23{slash}SD_COPI") (class "Default")
      (node (ref "J8") (pin "6") (pinfunction "6_6") (pintype "bidirectional"))
      (node (ref "U5") (pin "37") (pinfunction "PICO3/IO23_37") (pintype "bidirectional"))
    )
    (net (code "22") (name "ESP_25{slash}SD_~{CS}") (class "Default")
      (node (ref "J8") (pin "5") (pinfunction "5_5") (pintype "bidirectional"))
      (node (ref "U5") (pin "10") (pinfunction "DAC1/IOA25_10") (pintype "bidirectional"))
    )
    (net (code "23") (name "ESP_26{slash}DAC2") (class "Default")
      (node (ref "U1") (pin "11") (pinfunction "X3_11") (pintype "bidirectional"))
      (node (ref "U5") (pin "11") (pinfunction "DAC2/IOA26_11") (pintype "bidirectional"))
    )
    (net (code "24") (name "ESP_27{slash}FAST_OFF") (class "Default")
      (node (ref "C20") (pin "2") (pinfunction "2_2") (pintype "passive"))
      (node (ref "Q3") (pin "G1") (pinfunction "G_G1") (pintype "bidirectional"))
      (node (ref "R24") (pin "1") (pinfunction "1_1") (pintype "passive"))
      (node (ref "U5") (pin "12") (pinfunction "IOA27_12") (pintype "bidirectional"))
    )
    (net (code "25") (name "ESP_32{slash}RADIO_TXO") (class "Default")
      (node (ref "J10") (pin "11") (pinfunction "11_11") (pintype "bidirectional"))
      (node (ref "U5") (pin "8") (pinfunction "XTAL_P/IOA32_8") (pintype "bidirectional"))
    )
    (net (code "26") (name "ESP_33{slash}RADIO_RXI") (class "Default")
      (node (ref "J10") (pin "10") (pinfunction "10_10") (pintype "bidirectional"))
      (node (ref "U5") (pin "9") (pinfunction "XTAL_N/IOA33_9") (pintype "bidirectional"))
    )
    (net (code "27") (name "ESP_DM") (class "Default")
      (node (ref "U6") (pin "6") (pinfunction "UD-_6") (pintype "bidirectional"))
      (node (ref "U8") (pin "3") (pinfunction "USBDM_DN2_3") (pintype "bidirectional"))
    )
    (net (code "28") (name "ESP_DP") (class "Default")
      (node (ref "U6") (pin "5") (pinfunction "UD+_5") (pintype "bidirectional"))
      (node (ref "U8") (pin "4") (pinfunction "USBDP_DN2_4") (pintype "bidirectional"))
    )
    (net (code "29") (name "ESP_I34{slash}RADIO_INT") (class "Default")
      (node (ref "J10") (pin "7") (pinfunction "7_7") (pintype "bidirectional"))
      (node (ref "U5") (pin "6") (pinfunction "IA34_6") (pintype "bidirectional"))
    )
    (net (code "30") (name "ESP_I35{slash}DEVICE_SENSE") (class "Default")
      (node (ref "R33") (pin "2") (pinfunction "2_2") (pintype "passive"))
      (node (ref "R34") (pin "1") (pinfunction "1_1") (pintype "passive"))
      (node (ref "U5") (pin "7") (pinfunction "IA35_7") (pintype "bidirectional"))
    )
    (net (code "31") (name "ESP_I36{slash}RADIO_RTSO") (class "Default")
      (node (ref "J10") (pin "9") (pinfunction "9_9") (pintype "bidirectional"))
      (node (ref "U5") (pin "4") (pinfunction "SENSOR_VP/IA36_4") (pintype "bidirectional"))
    )
    (net (code "32") (name "ESP_I39{slash}ADC39") (class "Default")
      (node (ref "U1") (pin "4") (pinfunction "Y3_4") (pintype "bidirectional"))
      (node (ref "U5") (pin "5") (pinfunction "SENSOR_VN/IA39_5") (pintype "bidirectional"))
    )
    (net (code "33") (name "EXTERNAL_SERIAL1_RXI") (class "Default")
      (node (ref "J18") (pin "1") (pinfunction "1_1") (pintype "bidirectional"))
      (node (ref "U1") (pin "3") (pinfunction "Y_3") (pintype "bidirectional"))
    )
    (net (code "34") (name "EXTERNAL_SERIAL1_TXO") (class "Default")
      (node (ref "J18") (pin "2") (pinfunction "2_2") (pintype "bidirectional"))
      (node (ref "U1") (pin "13") (pinfunction "X_13") (pintype "bidirectional"))
    )
    (net (code "35") (name "GND") (class "Default")
      (node (ref "C10") (pin "2") (pinfunction "2_2") (pintype "passive"))
      (node (ref "C11") (pin "2") (pinfunction "2_2") (pintype "passive"))
      (node (ref "C12") (pin "2") (pinfunction "2_2") (pintype "passive"))
      (node (ref "C13") (pin "2") (pinfunction "2_2") (pintype "passive"))
      (node (ref "C14") (pin "2") (pinfunction "2_2") (pintype "passive"))
      (node (ref "C15") (pin "2") (pinfunction "2_2") (pintype "passive"))
      (node (ref "C16") (pin "2") (pinfunction "2_2") (pintype "passive"))
      (node (ref "C17") (pin "2") (pinfunction "2_2") (pintype "passive"))
      (node (ref "C18") (pin "2") (pinfunction "2_2") (pintype "passive"))
      (node (ref "C19") (pin "1") (pinfunction "1_1") (pintype "passive"))
      (node (ref "C2") (pin "2") (pinfunction "2_2") (pintype "passive"))
      (node (ref "C21") (pin "2") (pinfunction "2_2") (pintype "passive"))
      (node (ref "C24") (pin "2") (pinfunction "2_2") (pintype "passive"))
      (node (ref "C25") (pin "2") (pinfunction "2_2") (pintype "passive"))
      (node (ref "C26") (pin "1") (pinfunction "1_1") (pintype "passive"))
      (node (ref "C27") (pin "2") (pinfunction "2_2") (pintype "passive"))
      (node (ref "C28") (pin "2") (pinfunction "2_2") (pintype "passive"))
      (node (ref "C29") (pin "2") (pinfunction "2_2") (pintype "passive"))
      (node (ref "C3") (pin "2") (pinfunction "2_2") (pintype "passive"))
      (node (ref "C30") (pin "2") (pinfunction "2_2") (pintype "passive"))
      (node (ref "C31") (pin "2") (pinfunction "2_2") (pintype "passive"))
      (node (ref "C32") (pin "2") (pinfunction "2_2") (pintype "passive"))
      (node (ref "C4") (pin "2") (pinfunction "2_2") (pintype "passive"))
      (node (ref "C5") (pin "1") (pinfunction "1_1") (pintype "passive"))
      (node (ref "C6") (pin "2") (pinfunction "2_2") (pintype "passive"))
      (node (ref "C7") (pin "1") (pinfunction "1_1") (pintype "passive"))
      (node (ref "C8") (pin "2") (pinfunction "2_2") (pintype "passive"))
      (node (ref "C9") (pin "1") (pinfunction "1_1") (pintype "passive"))
      (node (ref "D1") (pin "C") (pinfunction "C_C") (pintype "passive"))
      (node (ref "D5") (pin "2") (pinfunction "2_2") (pintype "bidirectional"))
      (node (ref "J1") (pin "1") (pinfunction "1_1") (pintype "power_in"))
      (node (ref "J10") (pin "1") (pinfunction "1_1") (pintype "bidirectional"))
      (node (ref "J10") (pin "2") (pinfunction "2_2") (pintype "bidirectional"))
      (node (ref "J14") (pin "2") (pinfunction "2_2") (pintype "passive"))
      (node (ref "J15") (pin "10") (pinfunction "10_10") (pintype "bidirectional"))
      (node (ref "J15") (pin "11") (pinfunction "11_11") (pintype "bidirectional"))
      (node (ref "J15") (pin "12") (pinfunction "12_12") (pintype "bidirectional"))
      (node (ref "J18") (pin "11") (pinfunction "11_11") (pintype "bidirectional"))
      (node (ref "J18") (pin "12") (pinfunction "12_12") (pintype "bidirectional"))
      (node (ref "J2") (pin "1") (pinfunction "GND_1") (pintype "bidirectional"))
      (node (ref "J2") (pin "2") (pinfunction "GND_2") (pintype "bidirectional"))
      (node (ref "J3") (pin "1") (pinfunction "1_1") (pintype "passive"))
      (node (ref "J7") (pin "1") (pinfunction "-_1") (pintype "bidirectional"))
      (node (ref "J8") (pin "1") (pinfunction "1_1") (pintype "bidirectional"))
      (node (ref "J9") (pin "3") (pinfunction "GND_3") (pintype "bidirectional"))
      (node (ref "J9") (pin "5") (pinfunction "GND_5") (pintype "bidirectional"))
      (node (ref "J9") (pin "7") (pinfunction "KEY_7") (pintype "bidirectional"))
      (node (ref "J9") (pin "9") (pinfunction "GNDDTCT_9") (pintype "bidirectional"))
      (node (ref "Q3") (pin "S1") (pinfunction "S_S1") (pintype "bidirectional"))
      (node (ref "R10") (pin "1") (pinfunction "1_1") (pintype "bidirectional"))
      (node (ref "R16") (pin "1") (pinfunction "1_1") (pintype "passive"))
      (node (ref "R17") (pin "1") (pinfunction "1_1") (pintype "passive"))
      (node (ref "R19") (pin "1") (pinfunction "1_1") (pintype "passive"))
      (node (ref "R30") (pin "1") (pinfunction "1_1") (pintype "passive"))
      (node (ref "R33") (pin "1") (pinfunction "1_1") (pintype "passive"))
      (node (ref "R5") (pin "2") (pinfunction "2_2") (pintype "passive"))
      (node (ref "R6") (pin "1") (pinfunction "1_1") (pintype "passive"))
      (node (ref "U1") (pin "6") (pinfunction "INH_6") (pintype "input"))
      (node (ref "U1") (pin "7") (pinfunction "VEE_7") (pintype "power_in"))
      (node (ref "U1") (pin "8") (pinfunction "GND_8") (pintype "power_in"))
      (node (ref "U10") (pin "5") (pinfunction "VSS_5") (pintype "bidirectional"))
      (node (ref "U12") (pin "2") (pinfunction "GND_2") (pintype "input"))
      (node (ref "U13") (pin "1") (pinfunction "GND_1") (pintype "passive"))
      (node (ref "U13") (pin "3") (pinfunction "GND_3") (pintype "passive"))
      (node (ref "U13") (pin "5") (pinfunction "GND_5") (pintype "passive"))
      (node (ref "U2") (pin "2") (pinfunction "GND_2") (pintype "input"))
      (node (ref "U3") (pin "1") (pinfunction "GND_1") (pintype "bidirectional"))
      (node (ref "U3") (pin "100") (pinfunction "GND_100") (pintype "bidirectional"))
      (node (ref "U3") (pin "101") (pinfunction "GND_101") (pintype "bidirectional"))
      (node (ref "U3") (pin "102") (pinfunction "GND_102") (pintype "bidirectional"))
      (node (ref "U3") (pin "12") (pinfunction "GND_12") (pintype "bidirectional"))
      (node (ref "U3") (pin "14") (pinfunction "GND_14") (pintype "bidirectional"))
      (node (ref "U3") (pin "3") (pinfunction "GND_3") (pintype "bidirectional"))
      (node (ref "U3") (pin "32") (pinfunction "GND_32") (pintype "bidirectional"))
      (node (ref "U3") (pin "37") (pinfunction "GND_37") (pintype "bidirectional"))
      (node (ref "U3") (pin "41") (pinfunction "GND_41") (pintype "bidirectional"))
      (node (ref "U3") (pin "48") (pinfunction "GND_48") (pintype "bidirectional"))
      (node (ref "U3") (pin "55") (pinfunction "GND_55") (pintype "bidirectional"))
      (node (ref "U3") (pin "56") (pinfunction "GND_56") (pintype "bidirectional"))
      (node (ref "U3") (pin "57") (pinfunction "GND_57") (pintype "bidirectional"))
      (node (ref "U3") (pin "58") (pinfunction "GND_58") (pintype "bidirectional"))
      (node (ref "U3") (pin "59") (pinfunction "GND_59") (pintype "bidirectional"))
      (node (ref "U3") (pin "60") (pinfunction "GND_60") (pintype "bidirectional"))
      (node (ref "U3") (pin "61") (pinfunction "GND_61") (pintype "bidirectional"))
      (node (ref "U3") (pin "62") (pinfunction "GND_62") (pintype "bidirectional"))
      (node (ref "U3") (pin "63") (pinfunction "GND_63") (pintype "bidirectional"))
      (node (ref "U3") (pin "64") (pinfunction "GND_64") (pintype "bidirectional"))
      (node (ref "U3") (pin "65") (pinfunction "GND_65") (pintype "bidirectional"))
      (node (ref "U3") (pin "66") (pinfunction "GND_66") (pintype "bidirectional"))
      (node (ref "U3") (pin "67") (pinfunction "GND_67") (pintype "bidirectional"))
      (node (ref "U3") (pin "68") (pinfunction "GND_68") (pintype "bidirectional"))
      (node (ref "U3") (pin "69") (pinfunction "GND_69") (pintype "bidirectional"))
      (node (ref "U3") (pin "70") (pinfunction "GND_70") (pintype "bidirectional"))
      (node (ref "U3") (pin "71") (pinfunction "GND_71") (pintype "bidirectional"))
      (node (ref "U3") (pin "72") (pinfunction "GND_72") (pintype "bidirectional"))
      (node (ref "U3") (pin "73") (pinfunction "GND_73") (pintype "bidirectional"))
      (node (ref "U3") (pin "74") (pinfunction "GND_74") (pintype "bidirectional"))
      (node (ref "U3") (pin "75") (pinfunction "GND_75") (pintype "bidirectional"))
      (node (ref "U3") (pin "76") (pinfunction "GND_76") (pintype "bidirectional"))
      (node (ref "U3") (pin "77") (pinfunction "GND_77") (pintype "bidirectional"))
      (node (ref "U3") (pin "78") (pinfunction "GND_78") (pintype "bidirectional"))
      (node (ref "U3") (pin "79") (pinfunction "GND_79") (pintype "bidirectional"))
      (node (ref "U3") (pin "80") (pinfunction "GND_80") (pintype "bidirectional"))
      (node (ref "U3") (pin "81") (pinfunction "GND_81") (pintype "bidirectional"))
      (node (ref "U3") (pin "82") (pinfunction "GND_82") (pintype "bidirectional"))
      (node (ref "U3") (pin "83") (pinfunction "GND_83") (pintype "bidirectional"))
      (node (ref "U3") (pin "84") (pinfunction "GND_84") (pintype "bidirectional"))
      (node (ref "U3") (pin "85") (pinfunction "GND_85") (pintype "bidirectional"))
      (node (ref "U3") (pin "86") (pinfunction "GND_86") (pintype "bidirectional"))
      (node (ref "U3") (pin "87") (pinfunction "GND_87") (pintype "bidirectional"))
      (node (ref "U3") (pin "88") (pinfunction "GND_88") (pintype "bidirectional"))
      (node (ref "U3") (pin "89") (pinfunction "GND_89") (pintype "bidirectional"))
      (node (ref "U3") (pin "90") (pinfunction "GND_90") (pintype "bidirectional"))
      (node (ref "U3") (pin "91") (pinfunction "GND_91") (pintype "bidirectional"))
      (node (ref "U3") (pin "92") (pinfunction "GND_92") (pintype "bidirectional"))
      (node (ref "U3") (pin "93") (pinfunction "GND_93") (pintype "bidirectional"))
      (node (ref "U3") (pin "94") (pinfunction "GND_94") (pintype "bidirectional"))
      (node (ref "U3") (pin "95") (pinfunction "GND_95") (pintype "bidirectional"))
      (node (ref "U3") (pin "96") (pinfunction "GND_96") (pintype "bidirectional"))
      (node (ref "U3") (pin "97") (pinfunction "GND_97") (pintype "bidirectional"))
      (node (ref "U3") (pin "98") (pinfunction "GND_98") (pintype "bidirectional"))
      (node (ref "U3") (pin "99") (pinfunction "GND_99") (pintype "bidirectional"))
      (node (ref "U4") (pin "2") (pinfunction "GND_2") (pintype "input"))
      (node (ref "U5") (pin "1") (pinfunction "GND_1") (pintype "bidirectional"))
      (node (ref "U5") (pin "15") (pinfunction "GND_15") (pintype "bidirectional"))
      (node (ref "U5") (pin "38") (pinfunction "GND_38") (pintype "bidirectional"))
      (node (ref "U5") (pin "GND") (pinfunction "GND_GND") (pintype "bidirectional"))
      (node (ref "U5") (pin "GNDT1") (pinfunction "GND_GNDT1") (pintype "bidirectional"))
      (node (ref "U5") (pin "GNDT2") (pinfunction "GND_GNDT2") (pintype "bidirectional"))
      (node (ref "U5") (pin "GNDT3") (pinfunction "GND_GNDT3") (pintype "bidirectional"))
      (node (ref "U5") (pin "GNDT4") (pinfunction "GND_GNDT4") (pintype "bidirectional"))
      (node (ref "U5") (pin "GNDT5") (pinfunction "GND_GNDT5") (pintype "bidirectional"))
      (node (ref "U5") (pin "GNDT6") (pinfunction "GND_GNDT6") (pintype "bidirectional"))
      (node (ref "U5") (pin "GNDT7") (pinfunction "GND_GNDT7") (pintype "bidirectional"))
      (node (ref "U5") (pin "GNDT8") (pinfunction "GND_GNDT8") (pintype "bidirectional"))
      (node (ref "U6") (pin "1") (pinfunction "GND_1") (pintype "bidirectional"))
      (node (ref "U7") (pin "1") (pinfunction "CTG_1") (pintype "input"))
      (node (ref "U7") (pin "4") (pinfunction "GND_4") (pintype "bidirectional"))
      (node (ref "U7") (pin "6") (pinfunction "QSTRT_6") (pintype "bidirectional"))
      (node (ref "U7") (pin "9") (pinfunction "GND_9") (pintype "bidirectional"))
      (node (ref "U8") (pin "11") (pinfunction "TEST_11") (pintype "bidirectional"))
      (node (ref "U8") (pin "EP") (pinfunction "GND_EP") (pintype "bidirectional"))
      (node (ref "U9") (pin "10") (pinfunction "GND_10") (pintype "power_in"))
      (node (ref "U9") (pin "12") (pinfunction "GND_12") (pintype "power_in"))
      (node (ref "U9") (pin "13") (pinfunction "GND_13") (pintype "power_in"))
      (node (ref "U9") (pin "24") (pinfunction "GND_24") (pintype "power_in"))
    )
    (net (code "36") (name "NEO_DM") (class "Default")
      (node (ref "R40") (pin "1") (pinfunction "1_1") (pintype "passive"))
      (node (ref "U8") (pin "6") (pinfunction "USBDM_DN3_6") (pintype "bidirectional"))
    )
    (net (code "37") (name "NEO_DP") (class "Default")
      (node (ref "R39") (pin "1") (pinfunction "1_1") (pintype "passive"))
      (node (ref "U8") (pin "7") (pinfunction "USBDP_DN3_7") (pintype "bidirectional"))
    )
    (net (code "38") (name "NEO_RF_IN") (class "Default")
      (node (ref "R43") (pin "2") (pinfunction "2_2") (pintype "passive"))
      (node (ref "U13") (pin "6") (pinfunction "OUTPUT2_6") (pintype "output"))
      (node (ref "U9") (pin "11") (pinfunction "RF_IN_11") (pintype "input"))
    )
    (net (code "39") (name "Net-(C32-Pad1)") (class "Default")
      (node (ref "C32") (pin "1") (pinfunction "1_1") (pintype "passive"))
      (node (ref "FB2") (pin "2") (pinfunction "2_2") (pintype "passive"))
      (node (ref "R44") (pin "2") (pinfunction "2_2") (pintype "passive"))
    )
    (net (code "40") (name "Net-(D1-PadA)") (class "Default")
      (node (ref "D1") (pin "A") (pinfunction "A_A") (pintype "passive"))
      (node (ref "R11") (pin "1") (pinfunction "1_1") (pintype "passive"))
    )
    (net (code "41") (name "Net-(J2-SIGNAL)") (class "Default")
      (node (ref "C33") (pin "1") (pinfunction "1_1") (pintype "passive"))
      (node (ref "D5") (pin "1") (pinfunction "1_1") (pintype "bidirectional"))
      (node (ref "FB2") (pin "1") (pinfunction "1_1") (pintype "passive"))
      (node (ref "J2") (pin "FEED") (pinfunction "SIGNAL_FEED") (pintype "bidirectional"))
    )
    (net (code "42") (name "Net-(J7-+)") (class "Default")
      (node (ref "J7") (pin "2") (pinfunction "+_2") (pintype "bidirectional"))
      (node (ref "MEAS2") (pin "1") (pinfunction "1_1") (pintype "passive"))
      (node (ref "MEAS2") (pin "3") (pinfunction "1_3") (pintype "passive"))
    )
    (net (code "43") (name "Net-(JP3-Pad1)") (class "Default")
      (node (ref "JP3") (pin "1") (pinfunction "1_1") (pintype "passive"))
      (node (ref "R41") (pin "2") (pinfunction "2_2") (pintype "passive"))
    )
    (net (code "44") (name "Net-(JP4-Pad1)") (class "Default")
      (node (ref "JP4") (pin "1") (pinfunction "1_1") (pintype "passive"))
      (node (ref "R42") (pin "2") (pinfunction "2_2") (pintype "passive"))
    )
    (net (code "45") (name "Net-(JP7-Pad1)") (class "Default")
      (node (ref "JP7") (pin "1") (pinfunction "1_1") (pintype "passive"))
      (node (ref "R12") (pin "2") (pinfunction "2_2") (pintype "passive"))
    )
    (net (code "46") (name "Net-(JP7-Pad3)") (class "Default")
      (node (ref "JP7") (pin "3") (pinfunction "3_3") (pintype "passive"))
      (node (ref "R7") (pin "2") (pinfunction "2_2") (pintype "passive"))
    )
    (net (code "47") (name "Net-(Q2A-B)") (class "Default")
      (node (ref "Q2") (pin "5") (pinfunction "B_5") (pintype "passive"))
      (node (ref "R23") (pin "2") (pinfunction "2_2") (pintype "passive"))
    )
    (net (code "48") (name "Net-(Q2A-E)") (class "Default")
      (node (ref "Q2") (pin "4") (pinfunction "E_4") (pintype "passive"))
      (node (ref "R29") (pin "1") (pinfunction "1_1") (pintype "passive"))
      (node (ref "U6") (pin "14") (pinfunction "~{RTS}_14") (pintype "bidirectional"))
    )
    (net (code "49") (name "Net-(Q2B-B)") (class "Default")
      (node (ref "Q2") (pin "2") (pinfunction "B_2") (pintype "passive"))
      (node (ref "R29") (pin "2") (pinfunction "2_2") (pintype "passive"))
    )
    (net (code "50") (name "Net-(Q2B-E)") (class "Default")
      (node (ref "Q2") (pin "1") (pinfunction "E_1") (pintype "passive"))
      (node (ref "R23") (pin "1") (pinfunction "1_1") (pintype "passive"))
      (node (ref "U6") (pin "13") (pinfunction "~{DTR}_13") (pintype "bidirectional"))
    )
    (net (code "51") (name "Net-(Q3A-D)") (class "Default")
      (node (ref "C22") (pin "1") (pinfunction "1_1") (pintype "passive"))
      (node (ref "C23") (pin "2") (pinfunction "2_2") (pintype "passive"))
      (node (ref "Q3") (pin "D1") (pinfunction "D_D1") (pintype "bidirectional"))
      (node (ref "Q3") (pin "G2") (pinfunction "G_G2") (pintype "bidirectional"))
      (node (ref "R26") (pin "1") (pinfunction "1_1") (pintype "passive"))
    )
    (net (code "52") (name "Net-(R10-Pad2)") (class "Default")
      (node (ref "R10") (pin "2") (pinfunction "2_2") (pintype "bidirectional"))
      (node (ref "R30") (pin "2") (pinfunction "2_2") (pintype "passive"))
      (node (ref "R8") (pin "2") (pinfunction "2_2") (pintype "passive"))
    )
    (net (code "53") (name "Net-(U3-EXTINT)") (class "Default")
      (node (ref "R2") (pin "1") (pinfunction "1_1") (pintype "passive"))
      (node (ref "U3") (pin "51") (pinfunction "EXTINT_51") (pintype "bidirectional"))
    )
    (net (code "54") (name "Net-(U3-GEO_STAT)") (class "Default")
      (node (ref "R48") (pin "1") (pinfunction "1_1") (pintype "passive"))
      (node (ref "U3") (pin "19") (pinfunction "GEO_STAT_19") (pintype "bidirectional"))
    )
    (net (code "55") (name "Net-(U3-RTK_STAT)") (class "Default")
      (node (ref "R47") (pin "1") (pinfunction "1_1") (pintype "passive"))
      (node (ref "U3") (pin "20") (pinfunction "RTK_STAT_20") (pintype "bidirectional"))
    )
    (net (code "56") (name "Net-(U3-RX2)") (class "Default")
      (node (ref "R46") (pin "1") (pinfunction "1_1") (pintype "passive"))
      (node (ref "U3") (pin "26") (pinfunction "RX2_26") (pintype "bidirectional"))
    )
    (net (code "57") (name "Net-(U3-RX{slash}MOSI)") (class "Default")
      (node (ref "R15") (pin "1") (pinfunction "1_1") (pintype "passive"))
      (node (ref "U3") (pin "43") (pinfunction "RX/MOSI_43") (pintype "bidirectional"))
    )
    (net (code "58") (name "Net-(U3-SCL{slash}CLK)") (class "Default")
      (node (ref "R9") (pin "1") (pinfunction "1_1") (pintype "passive"))
      (node (ref "U3") (pin "45") (pinfunction "SCL/CLK_45") (pintype "bidirectional"))
    )
    (net (code "59") (name "Net-(U3-SDA{slash}~{CS})") (class "Default")
      (node (ref "R4") (pin "1") (pinfunction "1_1") (pintype "passive"))
      (node (ref "U3") (pin "44") (pinfunction "SDA/~{CS}_44") (pintype "bidirectional"))
    )
    (net (code "60") (name "Net-(U3-TIMEPULSE)") (class "Default")
      (node (ref "R49") (pin "1") (pinfunction "1_1") (pintype "passive"))
      (node (ref "U3") (pin "53") (pinfunction "TIMEPULSE_53") (pintype "bidirectional"))
    )
    (net (code "61") (name "Net-(U3-TX2)") (class "Default")
      (node (ref "R45") (pin "1") (pinfunction "1_1") (pintype "passive"))
      (node (ref "U3") (pin "27") (pinfunction "TX2_27") (pintype "bidirectional"))
    )
    (net (code "62") (name "Net-(U3-TX_READY)") (class "Default")
      (node (ref "R14") (pin "1") (pinfunction "1_1") (pintype "passive"))
      (node (ref "U3") (pin "46") (pinfunction "TX_READY_46") (pintype "bidirectional"))
    )
    (net (code "63") (name "Net-(U3-TX{slash}MISO)") (class "Default")
      (node (ref "R3") (pin "1") (pinfunction "1_1") (pintype "passive"))
      (node (ref "U3") (pin "42") (pinfunction "TX/MISO_42") (pintype "bidirectional"))
    )
    (net (code "64") (name "Net-(U3-USB_D+)") (class "Default")
      (node (ref "R27") (pin "2") (pinfunction "2_2") (pintype "passive"))
      (node (ref "U3") (pin "40") (pinfunction "USB_D+_40") (pintype "bidirectional"))
    )
    (net (code "65") (name "Net-(U3-USB_D-)") (class "Default")
      (node (ref "R28") (pin "2") (pinfunction "2_2") (pintype "passive"))
      (node (ref "U3") (pin "39") (pinfunction "USB_D-_39") (pintype "bidirectional"))
    )
    (net (code "66") (name "Net-(U3-~{RESET})") (class "Default")
      (node (ref "R1") (pin "1") (pinfunction "1_1") (pintype "passive"))
      (node (ref "U3") (pin "49") (pinfunction "~{RESET}_49") (pintype "bidirectional"))
    )
    (net (code "67") (name "Net-(U3-~{SAFEBOOT})") (class "Default")
      (node (ref "R50") (pin "1") (pinfunction "1_1") (pintype "passive"))
      (node (ref "U3") (pin "50") (pinfunction "~{SAFEBOOT}_50") (pintype "bidirectional"))
    )
    (net (code "68") (name "Net-(U8-CRFILT)") (class "Default")
      (node (ref "C24") (pin "1") (pinfunction "1_1") (pintype "passive"))
      (node (ref "U8") (pin "14") (pinfunction "CRFILT_14") (pintype "bidirectional"))
    )
    (net (code "69") (name "Net-(U8-HS_IND{slash}CFG1)") (class "Default")
      (node (ref "R17") (pin "2") (pinfunction "2_2") (pintype "passive"))
      (node (ref "U8") (pin "25") (pinfunction "HS_IND/CFG1_25") (pintype "bidirectional"))
    )
    (net (code "70") (name "Net-(U8-PLLFILT)") (class "Default")
      (node (ref "C21") (pin "1") (pinfunction "1_1") (pintype "passive"))
      (node (ref "U8") (pin "34") (pinfunction "PLLFILT_34") (pintype "bidirectional"))
    )
    (net (code "71") (name "Net-(U8-RBIAS)") (class "Default")
      (node (ref "R5") (pin "1") (pinfunction "1_1") (pintype "passive"))
      (node (ref "U8") (pin "35") (pinfunction "RBIAS_35") (pintype "bidirectional"))
    )
    (net (code "72") (name "Net-(U8-SCL{slash}CFG0)") (class "Default")
      (node (ref "JP2") (pin "2") (pinfunction "2_2") (pintype "passive"))
      (node (ref "U8") (pin "24") (pinfunction "SCL/CFG0_24") (pintype "bidirectional"))
    )
    (net (code "73") (name "Net-(U8-SDA)") (class "Default")
      (node (ref "JP1") (pin "2") (pinfunction "2_2") (pintype "passive"))
      (node (ref "U8") (pin "22") (pinfunction "SDA_22") (pintype "bidirectional"))
    )
    (net (code "74") (name "Net-(U8-SUSP_IND)") (class "Default")
      (node (ref "R16") (pin "2") (pinfunction "2_2") (pintype "passive"))
      (node (ref "U8") (pin "28") (pinfunction "SUSP_IND_28") (pintype "bidirectional"))
    )
    (net (code "75") (name "Net-(U8-USBDM_UP)") (class "Default")
      (node (ref "R25") (pin "2") (pinfunction "2_2") (pintype "passive"))
      (node (ref "U8") (pin "30") (pinfunction "USBDM_UP_30") (pintype "bidirectional"))
    )
    (net (code "76") (name "Net-(U8-USBDP_UP)") (class "Default")
      (node (ref "R32") (pin "2") (pinfunction "2_2") (pintype "passive"))
      (node (ref "U8") (pin "31") (pinfunction "USBDP_UP_31") (pintype "bidirectional"))
    )
    (net (code "77") (name "Net-(U8-XTALIN)") (class "Default")
      (node (ref "C9") (pin "2") (pinfunction "2_2") (pintype "passive"))
      (node (ref "R13") (pin "2") (pinfunction "2_2") (pintype "passive"))
      (node (ref "U8") (pin "33") (pinfunction "XTALIN_33") (pintype "bidirectional"))
      (node (ref "Y1") (pin "3") (pinfunction "2_3") (pintype "passive"))
    )
    (net (code "78") (name "Net-(U8-XTALOUT)") (class "Default")
      (node (ref "C19") (pin "2") (pinfunction "2_2") (pintype "passive"))
      (node (ref "R13") (pin "1") (pinfunction "1_1") (pintype "passive"))
      (node (ref "U8") (pin "32") (pinfunction "XTALOUT_32") (pintype "bidirectional"))
      (node (ref "Y1") (pin "1") (pinfunction "1_1") (pintype "passive"))
    )
    (net (code "79") (name "Net-(U8-~{RESET})") (class "Default")
      (node (ref "C28") (pin "1") (pinfunction "1_1") (pintype "passive"))
      (node (ref "R18") (pin "1") (pinfunction "1_1") (pintype "passive"))
      (node (ref "U8") (pin "26") (pinfunction "~{RESET}_26") (pintype "bidirectional"))
    )
    (net (code "80") (name "Net-(U9-RXD1{slash}PICO)") (class "Default")
      (node (ref "R36") (pin "1") (pinfunction "1_1") (pintype "passive"))
      (node (ref "U9") (pin "21") (pinfunction "RXD1/PICO_21") (pintype "input"))
    )
    (net (code "81") (name "Net-(U9-RXD2)") (class "Default")
      (node (ref "R42") (pin "1") (pinfunction "1_1") (pintype "passive"))
      (node (ref "U9") (pin "4") (pinfunction "RXD2_4") (pintype "input"))
    )
    (net (code "82") (name "Net-(U9-SCL{slash}SCK)") (class "Default")
      (node (ref "R38") (pin "1") (pinfunction "1_1") (pintype "passive"))
      (node (ref "U9") (pin "19") (pinfunction "SCL/SCK_19") (pintype "bidirectional"))
    )
    (net (code "83") (name "Net-(U9-SDA{slash}~{CS})") (class "Default")
      (node (ref "R37") (pin "1") (pinfunction "1_1") (pintype "passive"))
      (node (ref "U9") (pin "18") (pinfunction "SDA/~{CS}_18") (pintype "bidirectional"))
    )
    (net (code "84") (name "Net-(U9-TXD1{slash}POCI)") (class "Default")
      (node (ref "R35") (pin "1") (pinfunction "1_1") (pintype "passive"))
      (node (ref "U9") (pin "20") (pinfunction "TXD1/POCI_20") (pintype "output"))
    )
    (net (code "85") (name "Net-(U9-TXD2)") (class "Default")
      (node (ref "R41") (pin "1") (pinfunction "1_1") (pintype "passive"))
      (node (ref "U9") (pin "3") (pinfunction "TXD2_3") (pintype "output"))
    )
    (net (code "86") (name "Net-(U9-USB_D+)") (class "Default")
      (node (ref "R39") (pin "2") (pinfunction "2_2") (pintype "passive"))
      (node (ref "U9") (pin "6") (pinfunction "USB_D+_6") (pintype "bidirectional"))
    )
    (net (code "87") (name "Net-(U9-USB_D-)") (class "Default")
      (node (ref "R40") (pin "2") (pinfunction "2_2") (pintype "passive"))
      (node (ref "U9") (pin "5") (pinfunction "USB_D-_5") (pintype "bidirectional"))
    )
    (net (code "88") (name "Net-(U9-~{RESET})") (class "Default")
      (node (ref "TP1") (pin "1") (pinfunction "1_1") (pintype "bidirectional"))
      (node (ref "U9") (pin "8") (pinfunction "~{RESET}_8") (pintype "input"))
    )
    (net (code "89") (name "Net-(U9-~{SAFEBOOT})") (class "Default")
      (node (ref "TP2") (pin "1") (pinfunction "1_1") (pintype "bidirectional"))
      (node (ref "U9") (pin "1") (pinfunction "~{SAFEBOOT}_1") (pintype "input"))
    )
    (net (code "90") (name "Net-(U10-PROG)") (class "Default")
      (node (ref "R6") (pin "2") (pinfunction "2_2") (pintype "passive"))
      (node (ref "U10") (pin "6") (pinfunction "PROG_6") (pintype "bidirectional"))
    )
    (net (code "91") (name "Net-(U10-THERM)") (class "Default")
      (node (ref "R8") (pin "1") (pinfunction "1_1") (pintype "passive"))
      (node (ref "U10") (pin "8") (pinfunction "THERM_8") (pintype "bidirectional"))
    )
    (net (code "92") (name "Net-(U13-INPUT)") (class "Default")
      (node (ref "C33") (pin "2") (pinfunction "2_2") (pintype "passive"))
      (node (ref "U13") (pin "2") (pinfunction "INPUT_2") (pintype "input"))
    )
    (net (code "93") (name "POWER_BTN") (class "Default")
      (node (ref "C23") (pin "1") (pinfunction "1_1") (pintype "passive"))
      (node (ref "D4") (pin "C") (pinfunction "C_C") (pintype "passive"))
      (node (ref "J8") (pin "2") (pinfunction "2_2") (pintype "bidirectional"))
      (node (ref "R31") (pin "1") (pinfunction "1_1") (pintype "passive"))
    )
    (net (code "94") (name "USB_DM") (class "Default")
      (node (ref "J18") (pin "8") (pinfunction "8_8") (pintype "bidirectional"))
      (node (ref "R25") (pin "1") (pinfunction "1_1") (pintype "passive"))
    )
    (net (code "95") (name "USB_DP") (class "Default")
      (node (ref "J18") (pin "7") (pinfunction "7_7") (pintype "bidirectional"))
      (node (ref "R32") (pin "1") (pinfunction "1_1") (pintype "passive"))
    )
    (net (code "96") (name "VBUS_DET") (class "Default")
      (node (ref "C29") (pin "1") (pinfunction "1_1") (pintype "passive"))
      (node (ref "R19") (pin "2") (pinfunction "2_2") (pintype "passive"))
      (node (ref "R21") (pin "1") (pinfunction "1_1") (pintype "passive"))
      (node (ref "U8") (pin "27") (pinfunction "VBUS_DET_27") (pintype "bidirectional"))
    )
    (net (code "97") (name "VOUT") (class "Default")
      (node (ref "C20") (pin "1") (pinfunction "1_1") (pintype "passive"))
      (node (ref "C27") (pin "1") (pinfunction "1_1") (pintype "passive"))
      (node (ref "C6") (pin "1") (pinfunction "1_1") (pintype "passive"))
      (node (ref "J10") (pin "12") (pinfunction "12_12") (pintype "bidirectional"))
      (node (ref "J15") (pin "6") (pinfunction "6_6") (pintype "bidirectional"))
      (node (ref "J15") (pin "7") (pinfunction "7_7") (pintype "bidirectional"))
      (node (ref "J15") (pin "8") (pinfunction "8_8") (pintype "bidirectional"))
      (node (ref "J15") (pin "9") (pinfunction "9_9") (pintype "bidirectional"))
      (node (ref "Q3") (pin "D2") (pinfunction "D_D2") (pintype "bidirectional"))
      (node (ref "R22") (pin "2") (pinfunction "2_2") (pintype "passive"))
      (node (ref "U12") (pin "1") (pinfunction "IN_1") (pintype "input"))
      (node (ref "U2") (pin "1") (pinfunction "IN_1") (pintype "input"))
      (node (ref "U2") (pin "3") (pinfunction "EN_3") (pintype "input"))
    )
    (net (code "98") (name "V_BATT") (class "Default")
      (node (ref "C15") (pin "1") (pinfunction "1_1") (pintype "passive"))
      (node (ref "C17") (pin "1") (pinfunction "1_1") (pintype "passive"))
      (node (ref "C3") (pin "1") (pinfunction "1_1") (pintype "passive"))
      (node (ref "D7") (pin "A") (pinfunction "A_A") (pintype "passive"))
      (node (ref "MEAS2") (pin "2") (pinfunction "2_2") (pintype "passive"))
      (node (ref "MEAS2") (pin "4") (pinfunction "2_4") (pintype "passive"))
      (node (ref "U10") (pin "10") (pinfunction "VBAT_10") (pintype "bidirectional"))
      (node (ref "U10") (pin "9") (pinfunction "VBAT_9") (pintype "bidirectional"))
      (node (ref "U4") (pin "1") (pinfunction "IN_1") (pintype "input"))
      (node (ref "U4") (pin "3") (pinfunction "EN_3") (pintype "input"))
      (node (ref "U7") (pin "2") (pinfunction "CELL_2") (pintype "input"))
      (node (ref "U7") (pin "3") (pinfunction "VDD_3") (pintype "bidirectional"))
    )
    (net (code "99") (name "V_RAW") (class "Default")
      (node (ref "C16") (pin "1") (pinfunction "1_1") (pintype "passive"))
      (node (ref "C22") (pin "2") (pinfunction "2_2") (pintype "passive"))
      (node (ref "D2") (pin "C") (pinfunction "C_C") (pintype "passive"))
      (node (ref "D7") (pin "C") (pinfunction "C_C") (pintype "passive"))
      (node (ref "Q3") (pin "S2") (pinfunction "S_S2") (pintype "bidirectional"))
      (node (ref "R26") (pin "2") (pinfunction "2_2") (pintype "passive"))
      (node (ref "R31") (pin "2") (pinfunction "2_2") (pintype "passive"))
      (node (ref "U10") (pin "1") (pinfunction "VDD_1") (pintype "bidirectional"))
      (node (ref "U10") (pin "2") (pinfunction "VDD_2") (pintype "bidirectional"))
    )
    (net (code "100") (name "V_USB") (class "Default")
      (node (ref "D2") (pin "A") (pinfunction "A_A") (pintype "passive"))
      (node (ref "J15") (pin "1") (pinfunction "1_1") (pintype "bidirectional"))
      (node (ref "J15") (pin "2") (pinfunction "2_2") (pintype "bidirectional"))
      (node (ref "J15") (pin "3") (pinfunction "3_3") (pintype "bidirectional"))
      (node (ref "J15") (pin "4") (pinfunction "4_4") (pintype "bidirectional"))
      (node (ref "J8") (pin "12") (pinfunction "12_12") (pintype "bidirectional"))
      (node (ref "R21") (pin "2") (pinfunction "2_2") (pintype "passive"))
    )
    (net (code "101") (name "ZED_BACKUP") (class "Default")
      (node (ref "C18") (pin "1") (pinfunction "1_1") (pintype "passive"))
      (node (ref "U3") (pin "36") (pinfunction "V_BKCP_36") (pintype "bidirectional"))
      (node (ref "U4") (pin "5") (pinfunction "OUT_5") (pintype "passive"))
    )
    (net (code "102") (name "ZED_DM") (class "Default")
      (node (ref "R28") (pin "1") (pinfunction "1_1") (pintype "passive"))
      (node (ref "U8") (pin "1") (pinfunction "USBDM_DN1_1") (pintype "bidirectional"))
    )
    (net (code "103") (name "ZED_DP") (class "Default")
      (node (ref "R27") (pin "1") (pinfunction "1_1") (pintype "passive"))
      (node (ref "U8") (pin "2") (pinfunction "USBDP_DN1_2") (pintype "bidirectional"))
    )
    (net (code "104") (name "ZED_EXTINT") (class "Default")
      (node (ref "R2") (pin "2") (pinfunction "2_2") (pintype "passive"))
      (node (ref "U1") (pin "5") (pinfunction "Y1_5") (pintype "bidirectional"))
    )
    (net (code "105") (name "ZED_FENCE_STAT") (class "Default")
      (node (ref "R48") (pin "2") (pinfunction "2_2") (pintype "passive"))
    )
    (net (code "106") (name "ZED_PPS_STAT") (class "Default")
      (node (ref "J4") (pin "2") (pinfunction "2_2") (pintype "passive"))
      (node (ref "R49") (pin "2") (pinfunction "2_2") (pintype "passive"))
      (node (ref "U1") (pin "14") (pinfunction "X1_14") (pintype "bidirectional"))
    )
    (net (code "107") (name "ZED_RF_IN") (class "Default")
      (node (ref "R43") (pin "1") (pinfunction "1_1") (pintype "passive"))
      (node (ref "U13") (pin "4") (pinfunction "OUTPUT1_4") (pintype "output"))
      (node (ref "U3") (pin "2") (pinfunction "RF_IN_2") (pintype "bidirectional"))
    )
    (net (code "108") (name "ZED_RTK_STAT") (class "Default")
      (node (ref "R47") (pin "2") (pinfunction "2_2") (pintype "passive"))
    )
    (net (code "109") (name "ZED_RXI2") (class "Default")
      (node (ref "J18") (pin "9") (pinfunction "9_9") (pintype "bidirectional"))
      (node (ref "JP3") (pin "2") (pinfunction "2_2") (pintype "passive"))
      (node (ref "R46") (pin "2") (pinfunction "2_2") (pintype "passive"))
    )
    (net (code "110") (name "ZED_TXO2") (class "Default")
      (node (ref "J18") (pin "10") (pinfunction "10_10") (pintype "bidirectional"))
      (node (ref "JP4") (pin "2") (pinfunction "2_2") (pintype "passive"))
      (node (ref "R45") (pin "2") (pinfunction "2_2") (pintype "passive"))
    )
    (net (code "111") (name "ZED_TX_READY") (class "Default")
      (node (ref "R14") (pin "2") (pinfunction "2_2") (pintype "passive"))
    )
    (net (code "112") (name "ZED_VCC_RF") (class "Default")
      (node (ref "R44") (pin "1") (pinfunction "1_1") (pintype "passive"))
      (node (ref "U3") (pin "7") (pinfunction "V_RF_7") (pintype "bidirectional"))
    )
    (net (code "113") (name "ZED_~{RESET}") (class "Default")
      (node (ref "R1") (pin "2") (pinfunction "2_2") (pintype "passive"))
    )
    (net (code "114") (name "ZED_~{SAFE}") (class "Default")
      (node (ref "R50") (pin "2") (pinfunction "2_2") (pintype "passive"))
    )
    (net (code "115") (name "unconnected-(J7-PAD1-PadNC1)") (class "Default")
      (node (ref "J7") (pin "NC1") (pinfunction "PAD1_NC1") (pintype "bidirectional"))
    )
    (net (code "116") (name "unconnected-(J7-PAD2-PadNC2)") (class "Default")
      (node (ref "J7") (pin "NC2") (pinfunction "PAD2_NC2") (pintype "bidirectional"))
    )
    (net (code "117") (name "unconnected-(J15-Pad5)") (class "Default")
      (node (ref "J15") (pin "5") (pinfunction "5_5") (pintype "bidirectional"))
    )
    (net (code "118") (name "unconnected-(R35-Pad2)") (class "Default")
      (node (ref "R35") (pin "2") (pinfunction "2_2") (pintype "passive"))
    )
    (net (code "119") (name "unconnected-(R36-Pad2)") (class "Default")
      (node (ref "R36") (pin "2") (pinfunction "2_2") (pintype "passive"))
    )
    (net (code "120") (name "unconnected-(U3-ANT_DETECT-Pad4)") (class "Default")
      (node (ref "U3") (pin "4") (pinfunction "ANT_DETECT_4") (pintype "bidirectional"))
    )
    (net (code "121") (name "unconnected-(U3-ANT_OFF-Pad5)") (class "Default")
      (node (ref "U3") (pin "5") (pinfunction "ANT_OFF_5") (pintype "bidirectional"))
    )
    (net (code "122") (name "unconnected-(U3-D_SEL-Pad47)") (class "Default")
      (node (ref "U3") (pin "47") (pinfunction "D_SEL_47") (pintype "bidirectional"))
    )
    (net (code "123") (name "unconnected-(U3-~{ANT_SHORT}-Pad6)") (class "Default")
      (node (ref "U3") (pin "6") (pinfunction "~{ANT_SHORT}_6") (pintype "bidirectional"))
    )
    (net (code "124") (name "unconnected-(U6-R232-Pad15)") (class "Default")
      (node (ref "U6") (pin "15") (pinfunction "R232_15") (pintype "bidirectional"))
    )
    (net (code "125") (name "unconnected-(U6-~{CTS}-Pad9)") (class "Default")
      (node (ref "U6") (pin "9") (pinfunction "~{CTS}_9") (pintype "bidirectional"))
    )
    (net (code "126") (name "unconnected-(U6-~{DCD}-Pad12)") (class "Default")
      (node (ref "U6") (pin "12") (pinfunction "~{DCD}_12") (pintype "bidirectional"))
    )
    (net (code "127") (name "unconnected-(U6-~{DSR}-Pad10)") (class "Default")
      (node (ref "U6") (pin "10") (pinfunction "~{DSR}_10") (pintype "bidirectional"))
    )
    (net (code "128") (name "unconnected-(U6-~{RI}-Pad11)") (class "Default")
      (node (ref "U6") (pin "11") (pinfunction "~{RI}_11") (pintype "bidirectional"))
    )
    (net (code "129") (name "unconnected-(U7-~{ALRT}-Pad5)") (class "Default")
      (node (ref "U7") (pin "5") (pinfunction "~{ALRT}_5") (pintype "bidirectional"))
    )
    (net (code "130") (name "unconnected-(U8-PRTPWR1-Pad12)") (class "Default")
      (node (ref "U8") (pin "12") (pinfunction "PRTPWR1_12") (pintype "bidirectional"))
    )
    (net (code "131") (name "unconnected-(U8-PRTPWR2-Pad16)") (class "Default")
      (node (ref "U8") (pin "16") (pinfunction "PRTPWR2_16") (pintype "bidirectional"))
    )
    (net (code "132") (name "unconnected-(U8-PRTPWR3-Pad18)") (class "Default")
      (node (ref "U8") (pin "18") (pinfunction "PRTPWR3_18") (pintype "bidirectional"))
    )
    (net (code "133") (name "unconnected-(U8-PRTPWR4-Pad20)") (class "Default")
      (node (ref "U8") (pin "20") (pinfunction "PRTPWR4_20") (pintype "bidirectional"))
    )
    (net (code "134") (name "unconnected-(U8-USBDM_DN4-Pad8)") (class "Default")
      (node (ref "U8") (pin "8") (pinfunction "USBDM_DN4_8") (pintype "bidirectional"))
    )
    (net (code "135") (name "unconnected-(U8-USBDP_DN4-Pad9)") (class "Default")
      (node (ref "U8") (pin "9") (pinfunction "USBDP_DN4_9") (pintype "bidirectional"))
    )
    (net (code "136") (name "unconnected-(U8-~{OCS1}-Pad13)") (class "Default")
      (node (ref "U8") (pin "13") (pinfunction "~{OCS1}_13") (pintype "bidirectional"))
    )
    (net (code "137") (name "unconnected-(U8-~{OCS2}-Pad17)") (class "Default")
      (node (ref "U8") (pin "17") (pinfunction "~{OCS2}_17") (pintype "bidirectional"))
    )
    (net (code "138") (name "unconnected-(U8-~{OCS3}-Pad19)") (class "Default")
      (node (ref "U8") (pin "19") (pinfunction "~{OCS3}_19") (pintype "bidirectional"))
    )
    (net (code "139") (name "unconnected-(U8-~{OCS4}-Pad21)") (class "Default")
      (node (ref "U8") (pin "21") (pinfunction "~{OCS4}_21") (pintype "bidirectional"))
    )
    (net (code "140") (name "unconnected-(U9-ANT_DETECT-Pad15)") (class "Default")
      (node (ref "U9") (pin "15") (pinfunction "ANT_DETECT_15") (pintype "input"))
    )
    (net (code "141") (name "unconnected-(U9-ANT_OFF-Pad14)") (class "Default")
      (node (ref "U9") (pin "14") (pinfunction "ANT_OFF_14") (pintype "output"))
    )
    (net (code "142") (name "unconnected-(U9-D_SEL-Pad2)") (class "Default")
      (node (ref "U9") (pin "2") (pinfunction "D_SEL_2") (pintype "input"))
    )
    (net (code "143") (name "unconnected-(U9-EXT_INT-Pad17)") (class "Default")
      (node (ref "U9") (pin "17") (pinfunction "EXT_INT_17") (pintype "input"))
    )
    (net (code "144") (name "unconnected-(U9-VCC_RF-Pad9)") (class "Default")
      (node (ref "U9") (pin "9") (pinfunction "VCC_RF_9") (pintype "output"))
    )
    (net (code "145") (name "unconnected-(U9-~{ANT_SHORT}-Pad16)") (class "Default")
      (node (ref "U9") (pin "16") (pinfunction "~{ANT_SHORT}_16") (pintype "output"))
    )
    (net (code "146") (name "unconnected-(U10-STAT2-Pad4)") (class "Default")
      (node (ref "U10") (pin "4") (pinfunction "STAT2_4") (pintype "bidirectional"))
    )
    (net (code "147") (name "unconnected-(U10-~{PG}-Pad7)") (class "Default")
      (node (ref "U10") (pin "7") (pinfunction "~{PG}_7") (pintype "bidirectional"))
    )
  )
)
